# All-in-one_Starter_Kit_for_Micro_bit_V1_.net
KiCad netlist of a schematic drawn in EAGLE
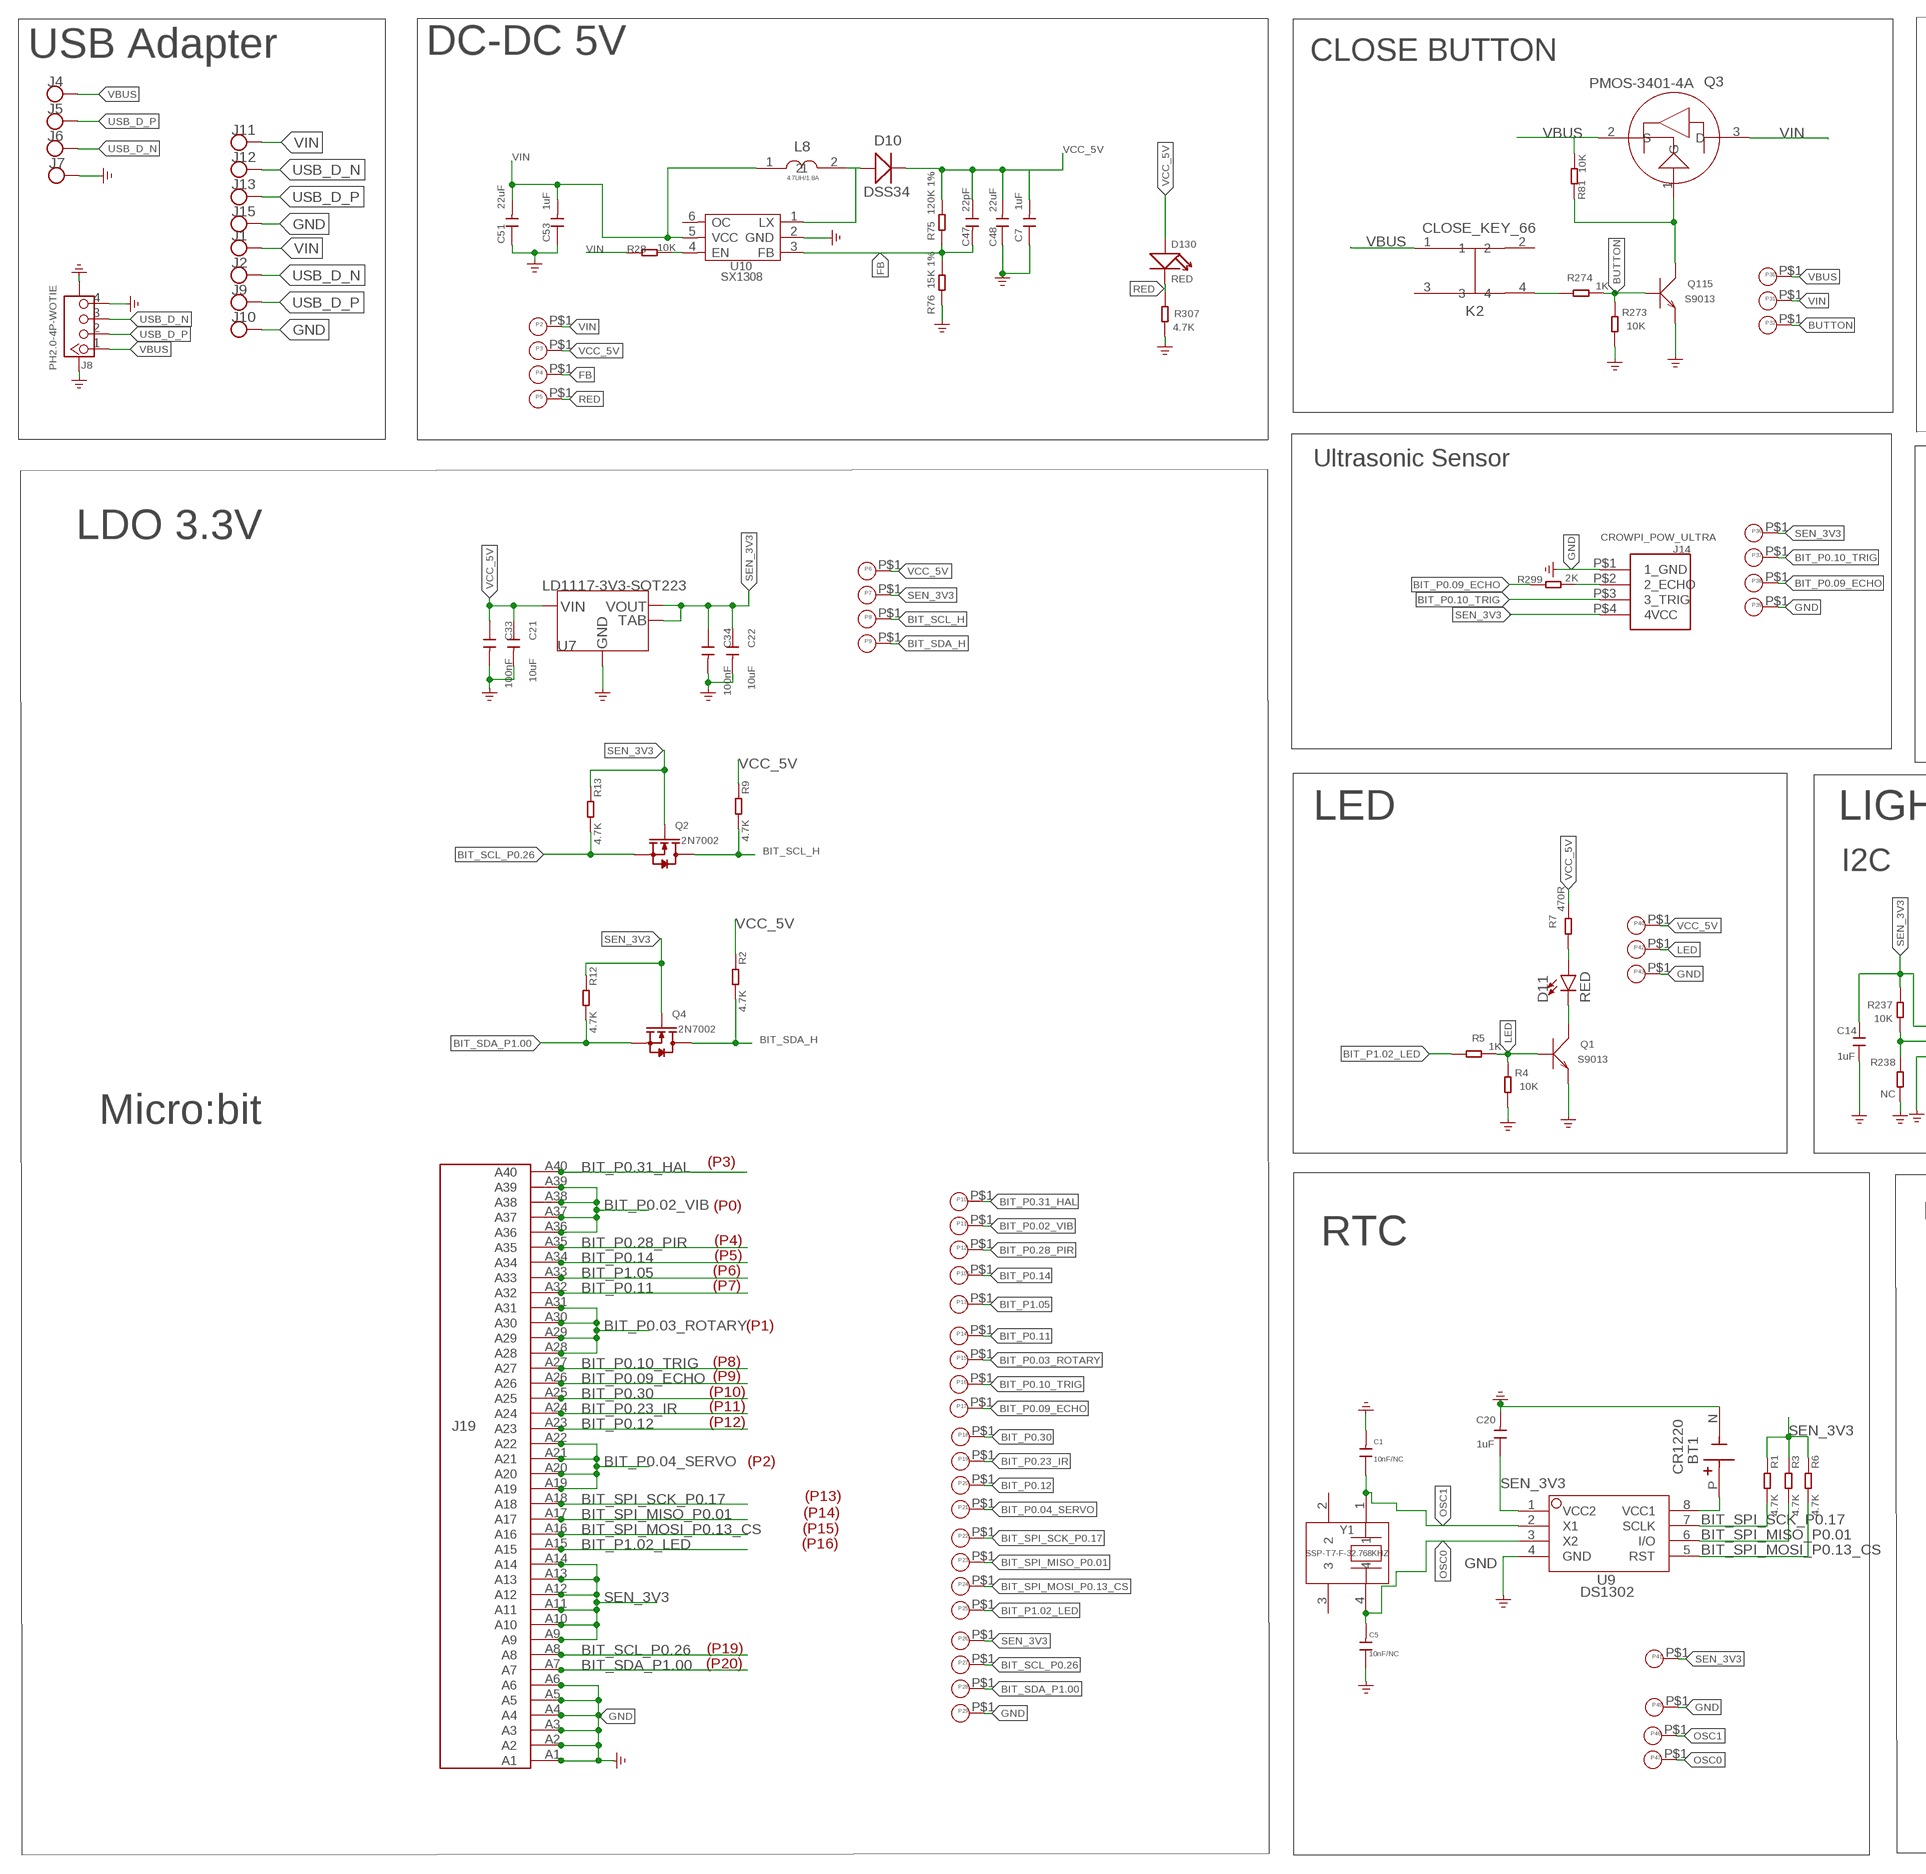
[diagram p0: schematic, sheet 1, part 1 of 2]
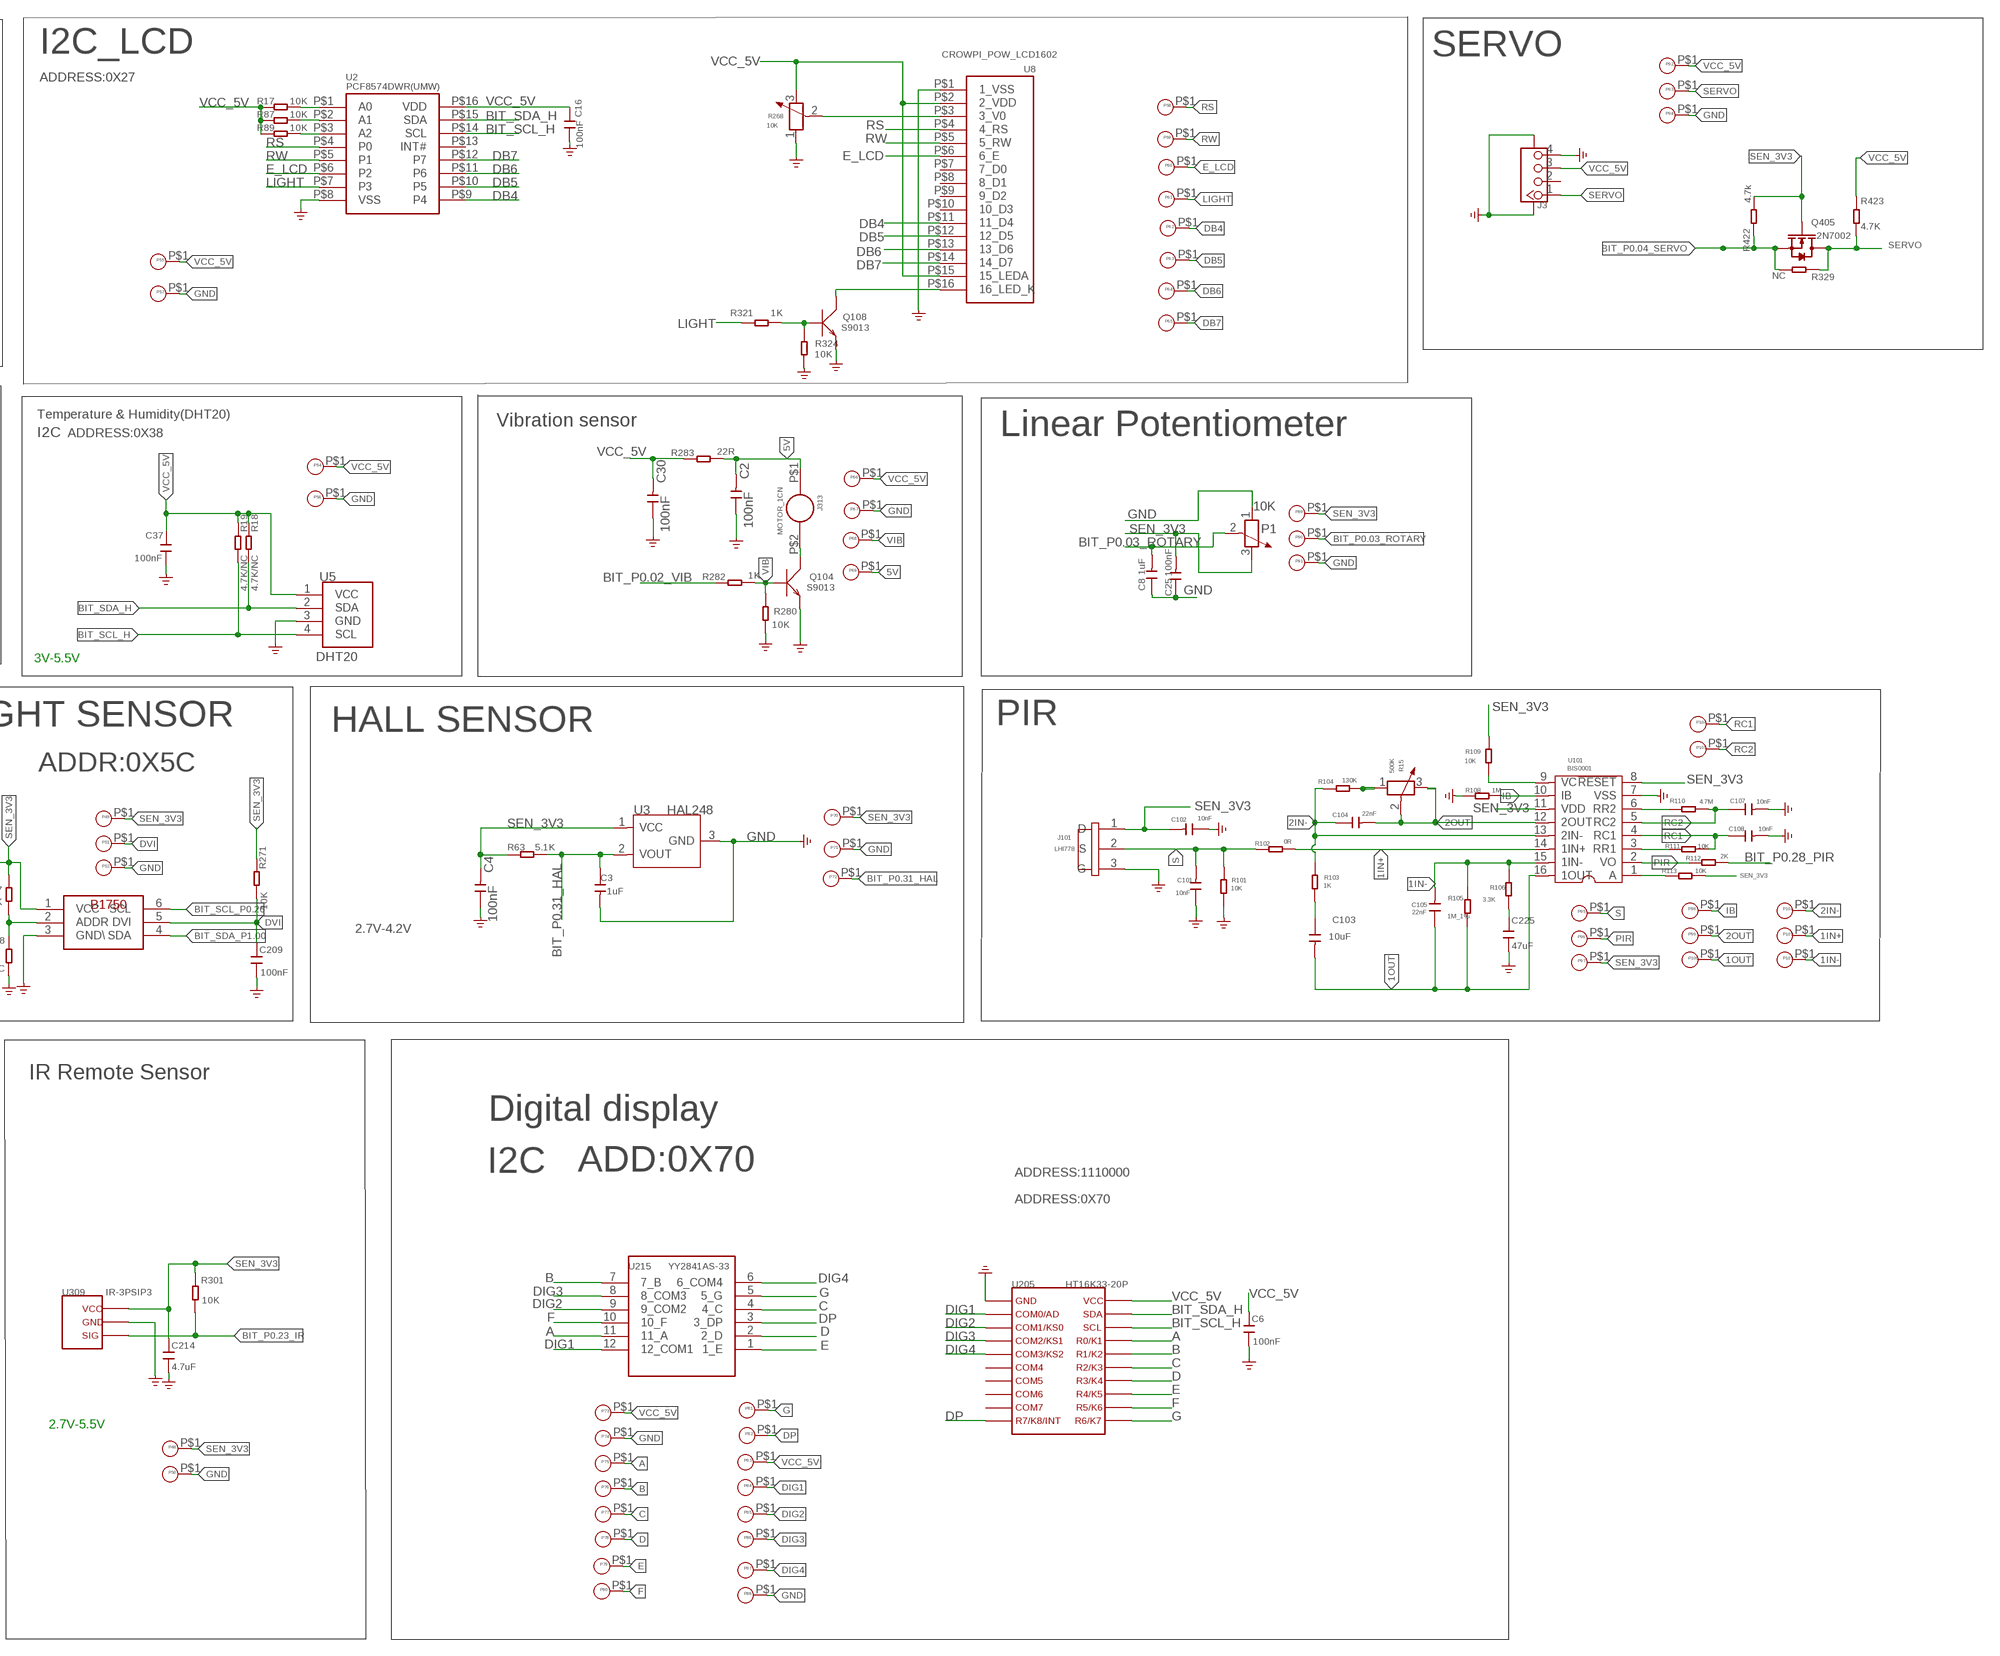
[diagram p1: schematic, sheet 1, part 2 of 2]

(export (version "E")
  (design (tool "Eeschema 10.0.6"))
  (components
    (comp (ref "BT1")
      (value "CR1220")
      (footprint "eagle-import:CR1220")
      (fields (field (name "MF") "Harwin") (field (name "MP") "S8411-45R"))
      (libsource (lib "eagle-import") (part "CR1220"))
    )
    (comp (ref "C1")
      (value "10nF/NC")
      (footprint "eagle-import:C0603")
      (libsource (lib "eagle-import") (part "C-0603"))
    )
    (comp (ref "C2")
      (value "100nF")
      (footprint "eagle-import:C0603")
      (libsource (lib "eagle-import") (part "C-0603"))
    )
    (comp (ref "C3")
      (value "1uF")
      (footprint "eagle-import:C0603")
      (libsource (lib "eagle-import") (part "C-0603"))
    )
    (comp (ref "C4")
      (value "100nF")
      (footprint "eagle-import:C0603")
      (libsource (lib "eagle-import") (part "C-0603"))
    )
    (comp (ref "C5")
      (value "10nF/NC")
      (footprint "eagle-import:C0603")
      (libsource (lib "eagle-import") (part "C-0603"))
    )
    (comp (ref "C6")
      (value "100nF")
      (footprint "eagle-import:0603")
      (libsource (lib "eagle-import") (part "cooper_C0603"))
    )
    (comp (ref "C7")
      (value "1uF")
      (footprint "eagle-import:C0603")
      (libsource (lib "eagle-import") (part "LoraWAN_Gateway_Mainboard_CAP"))
    )
    (comp (ref "C8")
      (value "1uF")
      (footprint "eagle-import:C0603")
      (libsource (lib "eagle-import") (part "C-0603"))
    )
    (comp (ref "C14")
      (value "1uF")
      (footprint "eagle-import:0603")
      (libsource (lib "eagle-import") (part "cooper_C0603"))
    )
    (comp (ref "C16")
      (value "100nF")
      (footprint "eagle-import:0603")
      (libsource (lib "eagle-import") (part "cooper_C0603"))
    )
    (comp (ref "C20")
      (value "1uF")
      (footprint "eagle-import:C0603")
      (libsource (lib "eagle-import") (part "CAP"))
    )
    (comp (ref "C21")
      (value "10uF")
      (footprint "eagle-import:C0603")
      (libsource (lib "eagle-import") (part "LoraWAN_Gateway_Mainboard_CAP"))
    )
    (comp (ref "C22")
      (value "10uF")
      (footprint "eagle-import:C0603")
      (libsource (lib "eagle-import") (part "LoraWAN_Gateway_Mainboard_CAP"))
    )
    (comp (ref "C25")
      (value "100nF")
      (footprint "eagle-import:C0603")
      (libsource (lib "eagle-import") (part "C-0603"))
    )
    (comp (ref "C30")
      (value "100nF")
      (footprint "eagle-import:C0603")
      (libsource (lib "eagle-import") (part "C-0603"))
    )
    (comp (ref "C33")
      (value "100nF")
      (footprint "eagle-import:C0603")
      (libsource (lib "eagle-import") (part "LoraWAN_Gateway_Mainboard_CAP"))
    )
    (comp (ref "C34")
      (value "100nF")
      (footprint "eagle-import:C0603")
      (libsource (lib "eagle-import") (part "LoraWAN_Gateway_Mainboard_CAP"))
    )
    (comp (ref "C37")
      (value "100nF")
      (footprint "eagle-import:0603")
      (libsource (lib "eagle-import") (part "cooper_C0603"))
    )
    (comp (ref "C47")
      (value "22pF")
      (footprint "eagle-import:C0603")
      (libsource (lib "eagle-import") (part "LoraWAN_Gateway_Mainboard_CAP"))
    )
    (comp (ref "C48")
      (value "22uF")
      (footprint "eagle-import:C0805")
      (libsource (lib "eagle-import") (part "LoraWAN_Gateway_Mainboard_CAPC0805"))
    )
    (comp (ref "C51")
      (value "22uF")
      (footprint "eagle-import:C0805")
      (libsource (lib "eagle-import") (part "LoraWAN_Gateway_Mainboard_CAPC0805"))
    )
    (comp (ref "C53")
      (value "1uF")
      (footprint "eagle-import:C0603")
      (libsource (lib "eagle-import") (part "LoraWAN_Gateway_Mainboard_CAP"))
    )
    (comp (ref "C101")
      (value "10nF")
      (footprint "eagle-import:C0603")
      (libsource (lib "eagle-import") (part "C-0603"))
    )
    (comp (ref "C102")
      (value "10nF")
      (footprint "eagle-import:C0603")
      (libsource (lib "eagle-import") (part "C-0603"))
    )
    (comp (ref "C103")
      (value "10uF")
      (footprint "eagle-import:0603")
      (libsource (lib "eagle-import") (part "C0603"))
    )
    (comp (ref "C104")
      (value "22nF")
      (footprint "eagle-import:C0603")
      (libsource (lib "eagle-import") (part "C-0603"))
    )
    (comp (ref "C105")
      (value "22nF")
      (footprint "eagle-import:C0603")
      (libsource (lib "eagle-import") (part "C-0603"))
    )
    (comp (ref "C107")
      (value "10nF")
      (footprint "eagle-import:C0603")
      (libsource (lib "eagle-import") (part "C-0603"))
    )
    (comp (ref "C108")
      (value "10nF")
      (footprint "eagle-import:C0603")
      (libsource (lib "eagle-import") (part "C-0603"))
    )
    (comp (ref "C209")
      (value "100nF")
      (footprint "eagle-import:0603")
      (libsource (lib "eagle-import") (part "cooper_C0603"))
    )
    (comp (ref "C214")
      (value "4.7uF")
      (footprint "eagle-import:0603")
      (libsource (lib "eagle-import") (part "cooper_C0603"))
    )
    (comp (ref "C225")
      (value "47uF")
      (footprint "eagle-import:0805")
      (libsource (lib "eagle-import") (part "C0805"))
    )
    (comp (ref "D10")
      (value "DSS34")
      (footprint "eagle-import:D_SOD123FL")
      (libsource (lib "eagle-import") (part "DIODE"))
    )
    (comp (ref "D11")
      (value "RED")
      (footprint "eagle-import:LED-8MM")
      (libsource (lib "eagle-import") (part "LED"))
    )
    (comp (ref "D130")
      (value "RED")
      (footprint "eagle-import:LED_0603_SMT")
      (libsource (lib "eagle-import") (part "LED_0603_SMT"))
    )
    (comp (ref "J1")
      (value "TP-SMDTP-SMD-2X4MM")
      (footprint "eagle-import:TP-SMD-2X4MM")
      (libsource (lib "eagle-import") (part "TP-SMDTP-SMD-2X4MM"))
    )
    (comp (ref "J2")
      (value "TP-SMDTP-SMD-2X4MM")
      (footprint "eagle-import:TP-SMD-2X4MM")
      (libsource (lib "eagle-import") (part "TP-SMDTP-SMD-2X4MM"))
    )
    (comp (ref "J3")
      (value "A_XBJ_CONNECTOR_TWIG-4P-2.0-SMD-FEMALE-REINFORCE90D")
      (footprint "eagle-import:A_XBJ_CONNECTOR_4P-SMD-2.0-90D")
      (libsource (lib "eagle-import") (part "A_XBJ_CONNECTOR_TWIG-4P-2.0-SMD-FEMALE-REINFORCE90D"))
    )
    (comp (ref "J4")
      (value "TP-SMDTP-SMD-2X4MM")
      (footprint "eagle-import:TP-SMD-2X4MM")
      (libsource (lib "eagle-import") (part "TP-SMDTP-SMD-2X4MM"))
    )
    (comp (ref "J5")
      (value "TP-SMDTP-SMD-2X4MM")
      (footprint "eagle-import:TP-SMD-2X4MM")
      (libsource (lib "eagle-import") (part "TP-SMDTP-SMD-2X4MM"))
    )
    (comp (ref "J6")
      (value "TP-SMDTP-SMD-2X4MM")
      (footprint "eagle-import:TP-SMD-2X4MM")
      (libsource (lib "eagle-import") (part "TP-SMDTP-SMD-2X4MM"))
    )
    (comp (ref "J7")
      (value "TP-SMDTP-SMD-2X4MM")
      (footprint "eagle-import:TP-SMD-2X4MM")
      (libsource (lib "eagle-import") (part "TP-SMDTP-SMD-2X4MM"))
    )
    (comp (ref "J8")
      (value "PH2.0-4P-WOTIE")
      (footprint "eagle-import:PH2.0-4P")
      (libsource (lib "eagle-import") (part "PH2.0-4P-WOTIE"))
    )
    (comp (ref "J9")
      (value "TP-SMDTP-SMD-2X4MM")
      (footprint "eagle-import:TP-SMD-2X4MM")
      (libsource (lib "eagle-import") (part "TP-SMDTP-SMD-2X4MM"))
    )
    (comp (ref "J10")
      (value "TP-SMDTP-SMD-2X4MM")
      (footprint "eagle-import:TP-SMD-2X4MM")
      (libsource (lib "eagle-import") (part "TP-SMDTP-SMD-2X4MM"))
    )
    (comp (ref "J11")
      (value "TP-SMDTP-SMD-2X4MM")
      (footprint "eagle-import:TP-SMD-2X4MM")
      (libsource (lib "eagle-import") (part "TP-SMDTP-SMD-2X4MM"))
    )
    (comp (ref "J12")
      (value "TP-SMDTP-SMD-2X4MM")
      (footprint "eagle-import:TP-SMD-2X4MM")
      (libsource (lib "eagle-import") (part "TP-SMDTP-SMD-2X4MM"))
    )
    (comp (ref "J13")
      (value "TP-SMDTP-SMD-2X4MM")
      (footprint "eagle-import:TP-SMD-2X4MM")
      (libsource (lib "eagle-import") (part "TP-SMDTP-SMD-2X4MM"))
    )
    (comp (ref "J14")
      (value "CROWPI_POW_ULTRA")
      (footprint "eagle-import:CROWPI_POW_ULTRA")
      (libsource (lib "eagle-import") (part "CROWPI_POW_ULTRA"))
    )
    (comp (ref "J15")
      (value "TP-SMDTP-SMD-2X4MM")
      (footprint "eagle-import:TP-SMD-2X4MM")
      (libsource (lib "eagle-import") (part "TP-SMDTP-SMD-2X4MM"))
    )
    (comp (ref "J19")
      (value "MICROBIT_SMD_40P")
      (footprint "eagle-import:MICROBIT_SMD_40P")
      (libsource (lib "eagle-import") (part "MICROBIT_SMD_40P"))
    )
    (comp (ref "J101")
      (value "LHI778")
      (footprint "eagle-import:3P-D8.1MM")
      (libsource (lib "eagle-import") (part "LHI778"))
    )
    (comp (ref "J313")
      (value "MOTOR_1CN")
      (footprint "eagle-import:MOTOR_1CM")
      (libsource (lib "eagle-import") (part "MOTOR_1CN"))
    )
    (comp (ref "K2")
      (value "CLOSE_KEY_66")
      (footprint "eagle-import:CLOSE_KEY_6_6")
      (libsource (lib "eagle-import") (part "CLOSE_KEY_66"))
    )
    (comp (ref "L8")
      (value "4.7UH/1.8A")
      (footprint "eagle-import:1008")
      (libsource (lib "eagle-import") (part "ZEMS252012-4R7M"))
    )
    (comp (ref "P1")
      (value "10K")
      (footprint "eagle-import:3P-SQUA-45.6X10X5.8H")
      (libsource (lib "eagle-import") (part "R-POTENTIOMETER"))
    )
    (comp (ref "P2")
      (value "PADPAD-1.0MM")
      (footprint "eagle-import:PAD-1.0MM")
      (libsource (lib "eagle-import") (part "PADPAD-1.0MM"))
    )
    (comp (ref "P3")
      (value "PADPAD-1.0MM")
      (footprint "eagle-import:PAD-1.0MM")
      (libsource (lib "eagle-import") (part "PADPAD-1.0MM"))
    )
    (comp (ref "P4")
      (value "PADPAD-1.0MM")
      (footprint "eagle-import:PAD-1.0MM")
      (libsource (lib "eagle-import") (part "PADPAD-1.0MM"))
    )
    (comp (ref "P5")
      (value "PADPAD-1.0MM")
      (footprint "eagle-import:PAD-1.0MM")
      (libsource (lib "eagle-import") (part "PADPAD-1.0MM"))
    )
    (comp (ref "P6")
      (value "PADPAD-1.0MM")
      (footprint "eagle-import:PAD-1.0MM")
      (libsource (lib "eagle-import") (part "PADPAD-1.0MM"))
    )
    (comp (ref "P7")
      (value "PADPAD-1.0MM")
      (footprint "eagle-import:PAD-1.0MM")
      (libsource (lib "eagle-import") (part "PADPAD-1.0MM"))
    )
    (comp (ref "P8")
      (value "PADPAD-1.0MM")
      (footprint "eagle-import:PAD-1.0MM")
      (libsource (lib "eagle-import") (part "PADPAD-1.0MM"))
    )
    (comp (ref "P9")
      (value "PADPAD-1.0MM")
      (footprint "eagle-import:PAD-1.0MM")
      (libsource (lib "eagle-import") (part "PADPAD-1.0MM"))
    )
    (comp (ref "P10")
      (value "PADPAD-1.0MM")
      (footprint "eagle-import:PAD-1.0MM")
      (libsource (lib "eagle-import") (part "PADPAD-1.0MM"))
    )
    (comp (ref "P11")
      (value "PADPAD-1.0MM")
      (footprint "eagle-import:PAD-1.0MM")
      (libsource (lib "eagle-import") (part "PADPAD-1.0MM"))
    )
    (comp (ref "P12")
      (value "PADPAD-1.0MM")
      (footprint "eagle-import:PAD-1.0MM")
      (libsource (lib "eagle-import") (part "PADPAD-1.0MM"))
    )
    (comp (ref "P13")
      (value "PADPAD-1.0MM")
      (footprint "eagle-import:PAD-1.0MM")
      (libsource (lib "eagle-import") (part "PADPAD-1.0MM"))
    )
    (comp (ref "P14")
      (value "PADPAD-1.0MM")
      (footprint "eagle-import:PAD-1.0MM")
      (libsource (lib "eagle-import") (part "PADPAD-1.0MM"))
    )
    (comp (ref "P15")
      (value "PADPAD-1.0MM")
      (footprint "eagle-import:PAD-1.0MM")
      (libsource (lib "eagle-import") (part "PADPAD-1.0MM"))
    )
    (comp (ref "P16")
      (value "PADPAD-1.0MM")
      (footprint "eagle-import:PAD-1.0MM")
      (libsource (lib "eagle-import") (part "PADPAD-1.0MM"))
    )
    (comp (ref "P17")
      (value "PADPAD-1.0MM")
      (footprint "eagle-import:PAD-1.0MM")
      (libsource (lib "eagle-import") (part "PADPAD-1.0MM"))
    )
    (comp (ref "P18")
      (value "PADPAD-1.0MM")
      (footprint "eagle-import:PAD-1.0MM")
      (libsource (lib "eagle-import") (part "PADPAD-1.0MM"))
    )
    (comp (ref "P19")
      (value "PADPAD-1.0MM")
      (footprint "eagle-import:PAD-1.0MM")
      (libsource (lib "eagle-import") (part "PADPAD-1.0MM"))
    )
    (comp (ref "P20")
      (value "PADPAD-1.0MM")
      (footprint "eagle-import:PAD-1.0MM")
      (libsource (lib "eagle-import") (part "PADPAD-1.0MM"))
    )
    (comp (ref "P21")
      (value "PADPAD-1.0MM")
      (footprint "eagle-import:PAD-1.0MM")
      (libsource (lib "eagle-import") (part "PADPAD-1.0MM"))
    )
    (comp (ref "P22")
      (value "PADPAD-1.0MM")
      (footprint "eagle-import:PAD-1.0MM")
      (libsource (lib "eagle-import") (part "PADPAD-1.0MM"))
    )
    (comp (ref "P23")
      (value "PADPAD-1.0MM")
      (footprint "eagle-import:PAD-1.0MM")
      (libsource (lib "eagle-import") (part "PADPAD-1.0MM"))
    )
    (comp (ref "P24")
      (value "PADPAD-1.0MM")
      (footprint "eagle-import:PAD-1.0MM")
      (libsource (lib "eagle-import") (part "PADPAD-1.0MM"))
    )
    (comp (ref "P25")
      (value "PADPAD-1.0MM")
      (footprint "eagle-import:PAD-1.0MM")
      (libsource (lib "eagle-import") (part "PADPAD-1.0MM"))
    )
    (comp (ref "P26")
      (value "PADPAD-1.0MM")
      (footprint "eagle-import:PAD-1.0MM")
      (libsource (lib "eagle-import") (part "PADPAD-1.0MM"))
    )
    (comp (ref "P27")
      (value "PADPAD-1.0MM")
      (footprint "eagle-import:PAD-1.0MM")
      (libsource (lib "eagle-import") (part "PADPAD-1.0MM"))
    )
    (comp (ref "P28")
      (value "PADPAD-1.0MM")
      (footprint "eagle-import:PAD-1.0MM")
      (libsource (lib "eagle-import") (part "PADPAD-1.0MM"))
    )
    (comp (ref "P29")
      (value "PADPAD-1.0MM")
      (footprint "eagle-import:PAD-1.0MM")
      (libsource (lib "eagle-import") (part "PADPAD-1.0MM"))
    )
    (comp (ref "P30")
      (value "PADPAD-1.0MM")
      (footprint "eagle-import:PAD-1.0MM")
      (libsource (lib "eagle-import") (part "PADPAD-1.0MM"))
    )
    (comp (ref "P31")
      (value "PADPAD-1.0MM")
      (footprint "eagle-import:PAD-1.0MM")
      (libsource (lib "eagle-import") (part "PADPAD-1.0MM"))
    )
    (comp (ref "P32")
      (value "PADPAD-1.0MM")
      (footprint "eagle-import:PAD-1.0MM")
      (libsource (lib "eagle-import") (part "PADPAD-1.0MM"))
    )
    (comp (ref "P36")
      (value "PADPAD-1.0MM")
      (footprint "eagle-import:PAD-1.0MM")
      (libsource (lib "eagle-import") (part "PADPAD-1.0MM"))
    )
    (comp (ref "P37")
      (value "PADPAD-1.0MM")
      (footprint "eagle-import:PAD-1.0MM")
      (libsource (lib "eagle-import") (part "PADPAD-1.0MM"))
    )
    (comp (ref "P38")
      (value "PADPAD-1.0MM")
      (footprint "eagle-import:PAD-1.0MM")
      (libsource (lib "eagle-import") (part "PADPAD-1.0MM"))
    )
    (comp (ref "P39")
      (value "PADPAD-1.0MM")
      (footprint "eagle-import:PAD-1.0MM")
      (libsource (lib "eagle-import") (part "PADPAD-1.0MM"))
    )
    (comp (ref "P40")
      (value "PADPAD-1.0MM")
      (footprint "eagle-import:PAD-1.0MM")
      (libsource (lib "eagle-import") (part "PADPAD-1.0MM"))
    )
    (comp (ref "P41")
      (value "PADPAD-1.0MM")
      (footprint "eagle-import:PAD-1.0MM")
      (libsource (lib "eagle-import") (part "PADPAD-1.0MM"))
    )
    (comp (ref "P42")
      (value "PADPAD-1.0MM")
      (footprint "eagle-import:PAD-1.0MM")
      (libsource (lib "eagle-import") (part "PADPAD-1.0MM"))
    )
    (comp (ref "P43")
      (value "PADPAD-1.0MM")
      (footprint "eagle-import:PAD-1.0MM")
      (libsource (lib "eagle-import") (part "PADPAD-1.0MM"))
    )
    (comp (ref "P45")
      (value "PADPAD-1.0MM")
      (footprint "eagle-import:PAD-1.0MM")
      (libsource (lib "eagle-import") (part "PADPAD-1.0MM"))
    )
    (comp (ref "P46")
      (value "PADPAD-1.0MM")
      (footprint "eagle-import:PAD-1.0MM")
      (libsource (lib "eagle-import") (part "PADPAD-1.0MM"))
    )
    (comp (ref "P47")
      (value "PADPAD-1.0MM")
      (footprint "eagle-import:PAD-1.0MM")
      (libsource (lib "eagle-import") (part "PADPAD-1.0MM"))
    )
    (comp (ref "P48")
      (value "PADPAD-1.0MM")
      (footprint "eagle-import:PAD-1.0MM")
      (libsource (lib "eagle-import") (part "PADPAD-1.0MM"))
    )
    (comp (ref "P49")
      (value "PADPAD-1.0MM")
      (footprint "eagle-import:PAD-1.0MM")
      (libsource (lib "eagle-import") (part "PADPAD-1.0MM"))
    )
    (comp (ref "P50")
      (value "PADPAD-1.0MM")
      (footprint "eagle-import:PAD-1.0MM")
      (libsource (lib "eagle-import") (part "PADPAD-1.0MM"))
    )
    (comp (ref "P51")
      (value "PADPAD-1.0MM")
      (footprint "eagle-import:PAD-1.0MM")
      (libsource (lib "eagle-import") (part "PADPAD-1.0MM"))
    )
    (comp (ref "P52")
      (value "PADPAD-1.0MM")
      (footprint "eagle-import:PAD-1.0MM")
      (libsource (lib "eagle-import") (part "PADPAD-1.0MM"))
    )
    (comp (ref "P54")
      (value "PADPAD-1.0MM")
      (footprint "eagle-import:PAD-1.0MM")
      (libsource (lib "eagle-import") (part "PADPAD-1.0MM"))
    )
    (comp (ref "P55")
      (value "PADPAD-1.0MM")
      (footprint "eagle-import:PAD-1.0MM")
      (libsource (lib "eagle-import") (part "PADPAD-1.0MM"))
    )
    (comp (ref "P56")
      (value "PADPAD-1.0MM")
      (footprint "eagle-import:PAD-1.0MM")
      (libsource (lib "eagle-import") (part "PADPAD-1.0MM"))
    )
    (comp (ref "P57")
      (value "PADPAD-1.0MM")
      (footprint "eagle-import:PAD-1.0MM")
      (libsource (lib "eagle-import") (part "PADPAD-1.0MM"))
    )
    (comp (ref "P58")
      (value "PADPAD-1.0MM")
      (footprint "eagle-import:PAD-1.0MM")
      (libsource (lib "eagle-import") (part "PADPAD-1.0MM"))
    )
    (comp (ref "P59")
      (value "PADPAD-1.0MM")
      (footprint "eagle-import:PAD-1.0MM")
      (libsource (lib "eagle-import") (part "PADPAD-1.0MM"))
    )
    (comp (ref "P60")
      (value "PADPAD-1.0MM")
      (footprint "eagle-import:PAD-1.0MM")
      (libsource (lib "eagle-import") (part "PADPAD-1.0MM"))
    )
    (comp (ref "P61")
      (value "PADPAD-1.0MM")
      (footprint "eagle-import:PAD-1.0MM")
      (libsource (lib "eagle-import") (part "PADPAD-1.0MM"))
    )
    (comp (ref "P62")
      (value "PADPAD-1.0MM")
      (footprint "eagle-import:PAD-1.0MM")
      (libsource (lib "eagle-import") (part "PADPAD-1.0MM"))
    )
    (comp (ref "P63")
      (value "PADPAD-1.0MM")
      (footprint "eagle-import:PAD-1.0MM")
      (libsource (lib "eagle-import") (part "PADPAD-1.0MM"))
    )
    (comp (ref "P64")
      (value "PADPAD-1.0MM")
      (footprint "eagle-import:PAD-1.0MM")
      (libsource (lib "eagle-import") (part "PADPAD-1.0MM"))
    )
    (comp (ref "P65")
      (value "PADPAD-1.0MM")
      (footprint "eagle-import:PAD-1.0MM")
      (libsource (lib "eagle-import") (part "PADPAD-1.0MM"))
    )
    (comp (ref "P66")
      (value "PADPAD-1.0MM")
      (footprint "eagle-import:PAD-1.0MM")
      (libsource (lib "eagle-import") (part "PADPAD-1.0MM"))
    )
    (comp (ref "P67")
      (value "PADPAD-1.0MM")
      (footprint "eagle-import:PAD-1.0MM")
      (libsource (lib "eagle-import") (part "PADPAD-1.0MM"))
    )
    (comp (ref "P68")
      (value "PADPAD-1.0MM")
      (footprint "eagle-import:PAD-1.0MM")
      (libsource (lib "eagle-import") (part "PADPAD-1.0MM"))
    )
    (comp (ref "P69")
      (value "PADPAD-1.0MM")
      (footprint "eagle-import:PAD-1.0MM")
      (libsource (lib "eagle-import") (part "PADPAD-1.0MM"))
    )
    (comp (ref "P70")
      (value "PADPAD-1.0MM")
      (footprint "eagle-import:PAD-1.0MM")
      (libsource (lib "eagle-import") (part "PADPAD-1.0MM"))
    )
    (comp (ref "P71")
      (value "PADPAD-1.0MM")
      (footprint "eagle-import:PAD-1.0MM")
      (libsource (lib "eagle-import") (part "PADPAD-1.0MM"))
    )
    (comp (ref "P72")
      (value "PADPAD-1.0MM")
      (footprint "eagle-import:PAD-1.0MM")
      (libsource (lib "eagle-import") (part "PADPAD-1.0MM"))
    )
    (comp (ref "P73")
      (value "PADPAD-1.0MM")
      (footprint "eagle-import:PAD-1.0MM")
      (libsource (lib "eagle-import") (part "PADPAD-1.0MM"))
    )
    (comp (ref "P74")
      (value "PADPAD-1.0MM")
      (footprint "eagle-import:PAD-1.0MM")
      (libsource (lib "eagle-import") (part "PADPAD-1.0MM"))
    )
    (comp (ref "P75")
      (value "PADPAD-1.0MM")
      (footprint "eagle-import:PAD-1.0MM")
      (libsource (lib "eagle-import") (part "PADPAD-1.0MM"))
    )
    (comp (ref "P76")
      (value "PADPAD-1.0MM")
      (footprint "eagle-import:PAD-1.0MM")
      (libsource (lib "eagle-import") (part "PADPAD-1.0MM"))
    )
    (comp (ref "P77")
      (value "PADPAD-1.0MM")
      (footprint "eagle-import:PAD-1.0MM")
      (libsource (lib "eagle-import") (part "PADPAD-1.0MM"))
    )
    (comp (ref "P78")
      (value "PADPAD-1.0MM")
      (footprint "eagle-import:PAD-1.0MM")
      (libsource (lib "eagle-import") (part "PADPAD-1.0MM"))
    )
    (comp (ref "P79")
      (value "PADPAD-1.0MM")
      (footprint "eagle-import:PAD-1.0MM")
      (libsource (lib "eagle-import") (part "PADPAD-1.0MM"))
    )
    (comp (ref "P80")
      (value "PADPAD-1.0MM")
      (footprint "eagle-import:PAD-1.0MM")
      (libsource (lib "eagle-import") (part "PADPAD-1.0MM"))
    )
    (comp (ref "P81")
      (value "PADPAD-1.0MM")
      (footprint "eagle-import:PAD-1.0MM")
      (libsource (lib "eagle-import") (part "PADPAD-1.0MM"))
    )
    (comp (ref "P82")
      (value "PADPAD-1.0MM")
      (footprint "eagle-import:PAD-1.0MM")
      (libsource (lib "eagle-import") (part "PADPAD-1.0MM"))
    )
    (comp (ref "P83")
      (value "PADPAD-1.0MM")
      (footprint "eagle-import:PAD-1.0MM")
      (libsource (lib "eagle-import") (part "PADPAD-1.0MM"))
    )
    (comp (ref "P84")
      (value "PADPAD-1.0MM")
      (footprint "eagle-import:PAD-1.0MM")
      (libsource (lib "eagle-import") (part "PADPAD-1.0MM"))
    )
    (comp (ref "P85")
      (value "PADPAD-1.0MM")
      (footprint "eagle-import:PAD-1.0MM")
      (libsource (lib "eagle-import") (part "PADPAD-1.0MM"))
    )
    (comp (ref "P86")
      (value "PADPAD-1.0MM")
      (footprint "eagle-import:PAD-1.0MM")
      (libsource (lib "eagle-import") (part "PADPAD-1.0MM"))
    )
    (comp (ref "P87")
      (value "PADPAD-1.0MM")
      (footprint "eagle-import:PAD-1.0MM")
      (libsource (lib "eagle-import") (part "PADPAD-1.0MM"))
    )
    (comp (ref "P88")
      (value "PADPAD-1.0MM")
      (footprint "eagle-import:PAD-1.0MM")
      (libsource (lib "eagle-import") (part "PADPAD-1.0MM"))
    )
    (comp (ref "P89")
      (value "PADPAD-1.0MM")
      (footprint "eagle-import:PAD-1.0MM")
      (libsource (lib "eagle-import") (part "PADPAD-1.0MM"))
    )
    (comp (ref "P90")
      (value "PADPAD-1.0MM")
      (footprint "eagle-import:PAD-1.0MM")
      (libsource (lib "eagle-import") (part "PADPAD-1.0MM"))
    )
    (comp (ref "P91")
      (value "PADPAD-1.0MM")
      (footprint "eagle-import:PAD-1.0MM")
      (libsource (lib "eagle-import") (part "PADPAD-1.0MM"))
    )
    (comp (ref "P92")
      (value "PADPAD-1.0MM")
      (footprint "eagle-import:PAD-1.0MM")
      (libsource (lib "eagle-import") (part "PADPAD-1.0MM"))
    )
    (comp (ref "P93")
      (value "PADPAD-1.0MM")
      (footprint "eagle-import:PAD-1.0MM")
      (libsource (lib "eagle-import") (part "PADPAD-1.0MM"))
    )
    (comp (ref "P94")
      (value "PADPAD-1.0MM")
      (footprint "eagle-import:PAD-1.0MM")
      (libsource (lib "eagle-import") (part "PADPAD-1.0MM"))
    )
    (comp (ref "P95")
      (value "PADPAD-1.0MM")
      (footprint "eagle-import:PAD-1.0MM")
      (libsource (lib "eagle-import") (part "PADPAD-1.0MM"))
    )
    (comp (ref "P96")
      (value "PADPAD-1.0MM")
      (footprint "eagle-import:PAD-1.0MM")
      (libsource (lib "eagle-import") (part "PADPAD-1.0MM"))
    )
    (comp (ref "P97")
      (value "PADPAD-1.0MM")
      (footprint "eagle-import:PAD-1.0MM")
      (libsource (lib "eagle-import") (part "PADPAD-1.0MM"))
    )
    (comp (ref "P98")
      (value "PADPAD-1.0MM")
      (footprint "eagle-import:PAD-1.0MM")
      (libsource (lib "eagle-import") (part "PADPAD-1.0MM"))
    )
    (comp (ref "P99")
      (value "PADPAD-1.0MM")
      (footprint "eagle-import:PAD-1.0MM")
      (libsource (lib "eagle-import") (part "PADPAD-1.0MM"))
    )
    (comp (ref "P100")
      (value "PADPAD-1.0MM")
      (footprint "eagle-import:PAD-1.0MM")
      (libsource (lib "eagle-import") (part "PADPAD-1.0MM"))
    )
    (comp (ref "P101")
      (value "PADPAD-1.0MM")
      (footprint "eagle-import:PAD-1.0MM")
      (libsource (lib "eagle-import") (part "PADPAD-1.0MM"))
    )
    (comp (ref "P102")
      (value "PADPAD-1.0MM")
      (footprint "eagle-import:PAD-1.0MM")
      (libsource (lib "eagle-import") (part "PADPAD-1.0MM"))
    )
    (comp (ref "P103")
      (value "PADPAD-1.0MM")
      (footprint "eagle-import:PAD-1.0MM")
      (libsource (lib "eagle-import") (part "PADPAD-1.0MM"))
    )
    (comp (ref "P104")
      (value "PADPAD-1.0MM")
      (footprint "eagle-import:PAD-1.0MM")
      (libsource (lib "eagle-import") (part "PADPAD-1.0MM"))
    )
    (comp (ref "P105")
      (value "PADPAD-1.0MM")
      (footprint "eagle-import:PAD-1.0MM")
      (libsource (lib "eagle-import") (part "PADPAD-1.0MM"))
    )
    (comp (ref "P106")
      (value "PADPAD-1.0MM")
      (footprint "eagle-import:PAD-1.0MM")
      (libsource (lib "eagle-import") (part "PADPAD-1.0MM"))
    )
    (comp (ref "Q1")
      (value "S9013")
      (footprint "eagle-import:SOT23@1")
      (libsource (lib "eagle-import") (part "TRANSISTOR-NPN-SOT23"))
    )
    (comp (ref "Q2")
      (value "2N7002")
      (footprint "eagle-import:SOT23")
      (libsource (lib "eagle-import") (part "MOSFET-N'SOT23'"))
    )
    (comp (ref "Q3")
      (value "PMOS-3401-4A")
      (footprint "eagle-import:DFN8_SOT-23")
      (libsource (lib "eagle-import") (part "DFN8_P-MOS-SOT23"))
    )
    (comp (ref "Q4")
      (value "2N7002")
      (footprint "eagle-import:SOT23")
      (libsource (lib "eagle-import") (part "MOSFET-N'SOT23'"))
    )
    (comp (ref "Q104")
      (value "S9013")
      (footprint "eagle-import:SOT23@1")
      (libsource (lib "eagle-import") (part "TRANSISTOR-NPN-SOT23"))
    )
    (comp (ref "Q108")
      (value "S9013")
      (footprint "eagle-import:SOT23@1")
      (libsource (lib "eagle-import") (part "TRANSISTOR-NPN-SOT23"))
    )
    (comp (ref "Q115")
      (value "S9013")
      (footprint "eagle-import:SOT23@1")
      (libsource (lib "eagle-import") (part "TRANSISTOR-NPN-SOT23"))
    )
    (comp (ref "Q405")
      (value "2N7002")
      (footprint "eagle-import:SOT23")
      (libsource (lib "eagle-import") (part "MOSFET-N'SOT23'"))
    )
    (comp (ref "R1")
      (value "4.7K")
      (footprint "eagle-import:R0603")
      (libsource (lib "eagle-import") (part "R0603"))
    )
    (comp (ref "R2")
      (value "4.7K")
      (footprint "eagle-import:R0603")
      (libsource (lib "eagle-import") (part "R0603"))
    )
    (comp (ref "R3")
      (value "4.7K")
      (footprint "eagle-import:R0603")
      (libsource (lib "eagle-import") (part "R0603"))
    )
    (comp (ref "R4")
      (value "10K")
      (footprint "eagle-import:R0603")
      (libsource (lib "eagle-import") (part "R-0603"))
    )
    (comp (ref "R5")
      (value "1K")
      (footprint "eagle-import:R0603")
      (libsource (lib "eagle-import") (part "R-0603"))
    )
    (comp (ref "R6")
      (value "4.7K")
      (footprint "eagle-import:R0603")
      (libsource (lib "eagle-import") (part "R0603"))
    )
    (comp (ref "R7")
      (value "470R")
      (footprint "eagle-import:R0603")
      (libsource (lib "eagle-import") (part "R-0603"))
    )
    (comp (ref "R9")
      (value "4.7K")
      (footprint "eagle-import:R0603")
      (libsource (lib "eagle-import") (part "R0603"))
    )
    (comp (ref "R12")
      (value "4.7K")
      (footprint "eagle-import:R0603")
      (libsource (lib "eagle-import") (part "R0603"))
    )
    (comp (ref "R13")
      (value "4.7K")
      (footprint "eagle-import:R0603")
      (libsource (lib "eagle-import") (part "R0603"))
    )
    (comp (ref "R15")
      (value "500K")
      (footprint "eagle-import:3P-SMD-SQUA-3.6X3.3")
      (libsource (lib "eagle-import") (part "R-POTENTIOMETER-SMD"))
    )
    (comp (ref "R17")
      (value "10K")
      (footprint "eagle-import:R0603")
      (libsource (lib "eagle-import") (part "R0603"))
    )
    (comp (ref "R18")
      (value "4.7K/NC")
      (footprint "eagle-import:R0603")
      (libsource (lib "eagle-import") (part "R0603"))
    )
    (comp (ref "R19")
      (value "4.7K/NC")
      (footprint "eagle-import:R0603")
      (libsource (lib "eagle-import") (part "R0603"))
    )
    (comp (ref "R28")
      (value "10K")
      (footprint "eagle-import:R0603-SP")
      (libsource (lib "eagle-import") (part "RES-0603"))
    )
    (comp (ref "R63")
      (value "5.1K")
      (footprint "eagle-import:R0603")
      (libsource (lib "eagle-import") (part "R-0603"))
    )
    (comp (ref "R75")
      (value "120K 1%")
      (footprint "eagle-import:R0603-SP")
      (libsource (lib "eagle-import") (part "RES-0603"))
    )
    (comp (ref "R76")
      (value "15K 1%")
      (footprint "eagle-import:R0603-SP")
      (libsource (lib "eagle-import") (part "RES-0603"))
    )
    (comp (ref "R81")
      (value "10K")
      (footprint "eagle-import:DISCRETE_R0603")
      (libsource (lib "eagle-import") (part "DISCRETE_R-0603"))
    )
    (comp (ref "R87")
      (value "10K")
      (footprint "eagle-import:R0603")
      (libsource (lib "eagle-import") (part "R0603"))
    )
    (comp (ref "R89")
      (value "10K")
      (footprint "eagle-import:R0603")
      (libsource (lib "eagle-import") (part "R0603"))
    )
    (comp (ref "R101")
      (value "10K")
      (footprint "eagle-import:R0603")
      (libsource (lib "eagle-import") (part "R-0603"))
    )
    (comp (ref "R102")
      (value "0R")
      (footprint "eagle-import:R0603")
      (libsource (lib "eagle-import") (part "R-0603"))
    )
    (comp (ref "R103")
      (value "1K")
      (footprint "eagle-import:R0603")
      (libsource (lib "eagle-import") (part "R-0603"))
    )
    (comp (ref "R104")
      (value "130K")
      (footprint "eagle-import:R0603")
      (libsource (lib "eagle-import") (part "R-0603"))
    )
    (comp (ref "R105")
      (value "1M_1%")
      (footprint "eagle-import:R0603")
      (libsource (lib "eagle-import") (part "R-0603"))
    )
    (comp (ref "R106")
      (value "3.3K")
      (footprint "eagle-import:R0603")
      (libsource (lib "eagle-import") (part "R-0603"))
    )
    (comp (ref "R108")
      (value "1M")
      (footprint "eagle-import:R0603")
      (libsource (lib "eagle-import") (part "R-0603"))
    )
    (comp (ref "R109")
      (value "10K")
      (footprint "eagle-import:R0603")
      (libsource (lib "eagle-import") (part "R-0603"))
    )
    (comp (ref "R110")
      (value "4.7M")
      (footprint "eagle-import:R0603")
      (libsource (lib "eagle-import") (part "R-0603"))
    )
    (comp (ref "R111")
      (value "10K")
      (footprint "eagle-import:R0603")
      (libsource (lib "eagle-import") (part "R-0603"))
    )
    (comp (ref "R112")
      (value "2K")
      (footprint "eagle-import:R0603")
      (libsource (lib "eagle-import") (part "R-0603"))
    )
    (comp (ref "R113")
      (value "10K")
      (footprint "eagle-import:R0603")
      (libsource (lib "eagle-import") (part "R-0603"))
    )
    (comp (ref "R237")
      (value "10K")
      (footprint "eagle-import:R0603")
      (libsource (lib "eagle-import") (part "R0603"))
    )
    (comp (ref "R238")
      (value "NC")
      (footprint "eagle-import:R0603")
      (libsource (lib "eagle-import") (part "R0603"))
    )
    (comp (ref "R268")
      (value "10K")
      (footprint "eagle-import:3P-SMD-SQUA-3.6X3.3")
      (libsource (lib "eagle-import") (part "R-POTENTIOMETER-SMD"))
    )
    (comp (ref "R271")
      (value "10K")
      (footprint "eagle-import:R0603")
      (libsource (lib "eagle-import") (part "R0603"))
    )
    (comp (ref "R273")
      (value "10K")
      (footprint "eagle-import:R0603")
      (libsource (lib "eagle-import") (part "R-0603"))
    )
    (comp (ref "R274")
      (value "1K")
      (footprint "eagle-import:R0603")
      (libsource (lib "eagle-import") (part "R-0603"))
    )
    (comp (ref "R280")
      (value "10K")
      (footprint "eagle-import:R0603")
      (libsource (lib "eagle-import") (part "R0603"))
    )
    (comp (ref "R282")
      (value "1K")
      (footprint "eagle-import:R0603")
      (libsource (lib "eagle-import") (part "R0603"))
    )
    (comp (ref "R283")
      (value "22R")
      (footprint "eagle-import:R0603")
      (libsource (lib "eagle-import") (part "R0603"))
    )
    (comp (ref "R299")
      (value "2K")
      (footprint "eagle-import:R0603")
      (libsource (lib "eagle-import") (part "R0603"))
    )
    (comp (ref "R301")
      (value "10K")
      (footprint "eagle-import:R0603")
      (libsource (lib "eagle-import") (part "R0603"))
    )
    (comp (ref "R307")
      (value "4.7K")
      (footprint "eagle-import:R0603")
      (libsource (lib "eagle-import") (part "R0603"))
    )
    (comp (ref "R321")
      (value "1K")
      (footprint "eagle-import:R0603")
      (libsource (lib "eagle-import") (part "R0603"))
    )
    (comp (ref "R324")
      (value "10K")
      (footprint "eagle-import:R0603")
      (libsource (lib "eagle-import") (part "R0603"))
    )
    (comp (ref "R329")
      (value "NC")
      (footprint "eagle-import:R0603")
      (libsource (lib "eagle-import") (part "RESR0603"))
    )
    (comp (ref "R422")
      (value "4.7k")
      (footprint "eagle-import:R0603")
      (libsource (lib "eagle-import") (part "RESR0603"))
    )
    (comp (ref "R423")
      (value "4.7K")
      (footprint "eagle-import:R0603")
      (libsource (lib "eagle-import") (part "RESR0603"))
    )
    (comp (ref "U1")
      (value "BH1750")
      (footprint "eagle-import:BH1750-WSOF-6")
      (libsource (lib "eagle-import") (part "BH1750"))
    )
    (comp (ref "U2")
      (value "PCF8574DWR(UMW)")
      (footprint "eagle-import:SO-16-300MIL")
      (libsource (lib "eagle-import") (part "PCF8574T/TR"))
    )
    (comp (ref "U3")
      (value "HAL248")
      (footprint "eagle-import:SOT-23W")
      (libsource (lib "eagle-import") (part "A1101"))
    )
    (comp (ref "U5")
      (value "DHT20")
      (footprint "eagle-import:CROWTAIL-DHT20-V1.0-20211013_DHT20")
      (libsource (lib "eagle-import") (part "CROWTAIL-DHT20-V1.0-20211013_DHT20"))
    )
    (comp (ref "U7")
      (value "LD1117-3V3-SOT223")
      (footprint "eagle-import:SOT223")
      (libsource (lib "eagle-import") (part "LD1117-3V3-SOT223"))
    )
    (comp (ref "U8")
      (value "CROWPI_POW_LCD1602")
      (footprint "eagle-import:CROWPI_POW_LCD1206")
      (libsource (lib "eagle-import") (part "CROWPI_POW_LCD1602"))
    )
    (comp (ref "U9")
      (value "DS1302")
      (footprint "eagle-import:SOP8")
      (libsource (lib "eagle-import") (part "DS1302"))
    )
    (comp (ref "U10")
      (value "SX1308")
      (footprint "eagle-import:SOT23-6L")
      (libsource (lib "eagle-import") (part "STUDY_SX1301"))
    )
    (comp (ref "U101")
      (value "BIS0001")
      (footprint "eagle-import:SOP16")
      (libsource (lib "eagle-import") (part "TM2291"))
    )
    (comp (ref "U205")
      (value "HT16K33-20P")
      (footprint "eagle-import:HT16K33-SOP20")
      (libsource (lib "eagle-import") (part "HT16K33-20P"))
    )
    (comp (ref "U215")
      (value "YY2841AS-33")
      (footprint "eagle-import:4-DIGITAL_DISPLAY")
      (libsource (lib "eagle-import") (part "4-DIGITAL_DISPLAY"))
    )
    (comp (ref "U309")
      (value "IR-3PSIP3")
      (footprint "eagle-import:VS1838B-SIP3")
      (libsource (lib "eagle-import") (part "IR-3PSIP3"))
    )
    (comp (ref "Y1")
      (value "SSP-T7-F-32.768KHZ")
      (footprint "eagle-import:MC-146")
      (libsource (lib "eagle-import") (part "SSP-T7-F-32.768KHZ"))
    )
  )
  (nets
    (net (code "1") (name "1IN+") (class "Default")
      (node (ref "P102") (pin "P$1") (pinfunction "P$1_P$1") (pintype "bidirectional"))
      (node (ref "R102") (pin "1") (pinfunction "1_1") (pintype "passive"))
      (node (ref "U101") (pin "14") (pinfunction "1IN+_14") (pintype "input"))
    )
    (net (code "2") (name "1IN-") (class "Default")
      (node (ref "C105") (pin "2") (pinfunction "2_2") (pintype "passive"))
      (node (ref "P103") (pin "P$1") (pinfunction "P$1_P$1") (pintype "bidirectional"))
      (node (ref "R105") (pin "2") (pinfunction "2_2") (pintype "passive"))
      (node (ref "R106") (pin "2") (pinfunction "2_2") (pintype "passive"))
      (node (ref "U101") (pin "15") (pinfunction "1IN-_15") (pintype "input"))
    )
    (net (code "3") (name "1OUT") (class "Default")
      (node (ref "C103") (pin "2") (pinfunction "2_2") (pintype "passive"))
      (node (ref "C105") (pin "1") (pinfunction "1_1") (pintype "passive"))
      (node (ref "P100") (pin "P$1") (pinfunction "P$1_P$1") (pintype "bidirectional"))
      (node (ref "R105") (pin "1") (pinfunction "1_1") (pintype "passive"))
      (node (ref "U101") (pin "16") (pinfunction "1OUT_16") (pintype "output"))
    )
    (net (code "4") (name "2IN-") (class "Default")
      (node (ref "C104") (pin "1") (pinfunction "1_1") (pintype "passive"))
      (node (ref "P101") (pin "P$1") (pinfunction "P$1_P$1") (pintype "bidirectional"))
      (node (ref "R103") (pin "2") (pinfunction "2_2") (pintype "passive"))
      (node (ref "R104") (pin "2") (pinfunction "2_2") (pintype "passive"))
      (node (ref "U101") (pin "13") (pinfunction "2IN-_13") (pintype "input"))
    )
    (net (code "5") (name "2OUT") (class "Default")
      (node (ref "C104") (pin "2") (pinfunction "2_2") (pintype "passive"))
      (node (ref "P99") (pin "P$1") (pinfunction "P$1_P$1") (pintype "bidirectional"))
      (node (ref "R15") (pin "2") (pinfunction "3_2") (pintype "passive"))
      (node (ref "R15") (pin "3") (pinfunction "2_3") (pintype "passive"))
      (node (ref "U101") (pin "12") (pinfunction "2OUT_12") (pintype "output"))
    )
    (net (code "6") (name "5V") (class "Default")
      (node (ref "C2") (pin "2") (pinfunction "2_2") (pintype "passive"))
      (node (ref "J313") (pin "P$1") (pinfunction "P$1_P$1") (pintype "bidirectional"))
      (node (ref "P69") (pin "P$1") (pinfunction "P$1_P$1") (pintype "bidirectional"))
      (node (ref "R283") (pin "2") (pinfunction "2_2") (pintype "passive"))
    )
    (net (code "7") (name "A") (class "Default")
      (node (ref "P75") (pin "P$1") (pinfunction "P$1_P$1") (pintype "bidirectional"))
      (node (ref "U205") (pin "P$17") (pinfunction "P$17_P$17") (pintype "bidirectional"))
      (node (ref "U215") (pin "11") (pinfunction "11_A_11") (pintype "bidirectional"))
    )
    (net (code "8") (name "B") (class "Default")
      (node (ref "P76") (pin "P$1") (pinfunction "P$1_P$1") (pintype "bidirectional"))
      (node (ref "U205") (pin "P$16") (pinfunction "P$16_P$16") (pintype "bidirectional"))
      (node (ref "U215") (pin "7") (pinfunction "7_B_7") (pintype "bidirectional"))
    )
    (net (code "9") (name "BIT_P0.02_VIB") (class "Default")
      (node (ref "J19") (pin "A36") (pinfunction "A36_A36") (pintype "bidirectional"))
      (node (ref "J19") (pin "A37") (pinfunction "A37_A37") (pintype "bidirectional"))
      (node (ref "J19") (pin "A38") (pinfunction "A38_A38") (pintype "bidirectional"))
      (node (ref "J19") (pin "A39") (pinfunction "A39_A39") (pintype "bidirectional"))
      (node (ref "P11") (pin "P$1") (pinfunction "P$1_P$1") (pintype "bidirectional"))
      (node (ref "R282") (pin "1") (pinfunction "1_1") (pintype "passive"))
    )
    (net (code "10") (name "BIT_P0.03_ROTARY") (class "Default")
      (node (ref "C8") (pin "2") (pinfunction "2_2") (pintype "passive"))
      (node (ref "J19") (pin "A28") (pinfunction "A28_A28") (pintype "bidirectional"))
      (node (ref "J19") (pin "A29") (pinfunction "A29_A29") (pintype "bidirectional"))
      (node (ref "J19") (pin "A30") (pinfunction "A30_A30") (pintype "bidirectional"))
      (node (ref "J19") (pin "A31") (pinfunction "A31_A31") (pintype "bidirectional"))
      (node (ref "P1") (pin "2") (pinfunction "3_2") (pintype "passive"))
      (node (ref "P15") (pin "P$1") (pinfunction "P$1_P$1") (pintype "bidirectional"))
      (node (ref "P90") (pin "P$1") (pinfunction "P$1_P$1") (pintype "bidirectional"))
    )
    (net (code "11") (name "BIT_P0.04_SERVO") (class "Default")
      (node (ref "J19") (pin "A19") (pinfunction "A19_A19") (pintype "bidirectional"))
      (node (ref "J19") (pin "A20") (pinfunction "A20_A20") (pintype "bidirectional"))
      (node (ref "J19") (pin "A21") (pinfunction "A21_A21") (pintype "bidirectional"))
      (node (ref "J19") (pin "A22") (pinfunction "A22_A22") (pintype "bidirectional"))
      (node (ref "P21") (pin "P$1") (pinfunction "P$1_P$1") (pintype "bidirectional"))
      (node (ref "Q405") (pin "2") (pinfunction "S_2") (pintype "passive"))
      (node (ref "R329") (pin "2") (pinfunction "2_2") (pintype "passive"))
      (node (ref "R422") (pin "1") (pinfunction "1_1") (pintype "passive"))
    )
    (net (code "12") (name "BIT_P0.09_ECHO") (class "Default")
      (node (ref "J19") (pin "A26") (pinfunction "A26_A26") (pintype "bidirectional"))
      (node (ref "P17") (pin "P$1") (pinfunction "P$1_P$1") (pintype "bidirectional"))
      (node (ref "P38") (pin "P$1") (pinfunction "P$1_P$1") (pintype "bidirectional"))
      (node (ref "R299") (pin "2") (pinfunction "2_2") (pintype "passive"))
    )
    (net (code "13") (name "BIT_P0.10_TRIG") (class "Default")
      (node (ref "J14") (pin "P$3") (pinfunction "3_TRIG_P$3") (pintype "bidirectional"))
      (node (ref "J19") (pin "A27") (pinfunction "A27_A27") (pintype "bidirectional"))
      (node (ref "P16") (pin "P$1") (pinfunction "P$1_P$1") (pintype "bidirectional"))
      (node (ref "P37") (pin "P$1") (pinfunction "P$1_P$1") (pintype "bidirectional"))
    )
    (net (code "14") (name "BIT_P0.11") (class "Default")
      (node (ref "J19") (pin "A32") (pinfunction "A32_A32") (pintype "bidirectional"))
      (node (ref "P14") (pin "P$1") (pinfunction "P$1_P$1") (pintype "bidirectional"))
    )
    (net (code "15") (name "BIT_P0.12") (class "Default")
      (node (ref "J19") (pin "A23") (pinfunction "A23_A23") (pintype "bidirectional"))
      (node (ref "P20") (pin "P$1") (pinfunction "P$1_P$1") (pintype "bidirectional"))
    )
    (net (code "16") (name "BIT_P0.14") (class "Default")
      (node (ref "J19") (pin "A34") (pinfunction "A34_A34") (pintype "bidirectional"))
      (node (ref "P106") (pin "P$1") (pinfunction "P$1_P$1") (pintype "bidirectional"))
    )
    (net (code "17") (name "BIT_P0.23_IR") (class "Default")
      (node (ref "J19") (pin "A24") (pinfunction "A24_A24") (pintype "bidirectional"))
      (node (ref "P19") (pin "P$1") (pinfunction "P$1_P$1") (pintype "bidirectional"))
      (node (ref "R301") (pin "2") (pinfunction "2_2") (pintype "passive"))
      (node (ref "U309") (pin "3") (pinfunction "P$3_3") (pintype "bidirectional"))
    )
    (net (code "18") (name "BIT_P0.28_PIR") (class "Default")
      (node (ref "J19") (pin "A35") (pinfunction "A35_A35") (pintype "bidirectional"))
      (node (ref "P12") (pin "P$1") (pinfunction "P$1_P$1") (pintype "bidirectional"))
      (node (ref "R112") (pin "1") (pinfunction "1_1") (pintype "passive"))
    )
    (net (code "19") (name "BIT_P0.30") (class "Default")
      (node (ref "J19") (pin "A25") (pinfunction "A25_A25") (pintype "bidirectional"))
      (node (ref "P18") (pin "P$1") (pinfunction "P$1_P$1") (pintype "bidirectional"))
    )
    (net (code "20") (name "BIT_P0.31_HAL") (class "Default")
      (node (ref "C3") (pin "1") (pinfunction "1_1") (pintype "passive"))
      (node (ref "J19") (pin "A40") (pinfunction "A40_A40") (pintype "bidirectional"))
      (node (ref "P10") (pin "P$1") (pinfunction "P$1_P$1") (pintype "bidirectional"))
      (node (ref "P72") (pin "P$1") (pinfunction "P$1_P$1") (pintype "bidirectional"))
      (node (ref "R63") (pin "1") (pinfunction "1_1") (pintype "passive"))
      (node (ref "U3") (pin "2") (pinfunction "VOUT_2") (pintype "output"))
    )
    (net (code "21") (name "BIT_P1.02_LED") (class "Default")
      (node (ref "J19") (pin "A15") (pinfunction "A15_A15") (pintype "bidirectional"))
      (node (ref "P25") (pin "P$1") (pinfunction "P$1_P$1") (pintype "bidirectional"))
      (node (ref "R5") (pin "2") (pinfunction "2_2") (pintype "passive"))
    )
    (net (code "22") (name "BIT_P1.05") (class "Default")
      (node (ref "J19") (pin "A33") (pinfunction "A33_A33") (pintype "bidirectional"))
      (node (ref "P13") (pin "P$1") (pinfunction "P$1_P$1") (pintype "bidirectional"))
    )
    (net (code "23") (name "BIT_SCL_H") (class "Default")
      (node (ref "P8") (pin "P$1") (pinfunction "P$1_P$1") (pintype "bidirectional"))
      (node (ref "Q2") (pin "3") (pinfunction "D_3") (pintype "passive"))
      (node (ref "R19") (pin "2") (pinfunction "2_2") (pintype "passive"))
      (node (ref "R9") (pin "2") (pinfunction "2_2") (pintype "passive"))
      (node (ref "U2") (pin "P$14") (pinfunction "SCL_P$14") (pintype "bidirectional"))
      (node (ref "U205") (pin "P$18") (pinfunction "P$18_P$18") (pintype "bidirectional"))
      (node (ref "U5") (pin "4") (pinfunction "SCL_4") (pintype "bidirectional"))
    )
    (net (code "24") (name "BIT_SCL_P0.26") (class "Default")
      (node (ref "J19") (pin "A8") (pinfunction "A8_A8") (pintype "bidirectional"))
      (node (ref "P27") (pin "P$1") (pinfunction "P$1_P$1") (pintype "bidirectional"))
      (node (ref "Q2") (pin "2") (pinfunction "S_2") (pintype "passive"))
      (node (ref "R13") (pin "2") (pinfunction "2_2") (pintype "passive"))
      (node (ref "U1") (pin "6") (pinfunction "SCL_6") (pintype "bidirectional"))
    )
    (net (code "25") (name "BIT_SDA_H") (class "Default")
      (node (ref "P9") (pin "P$1") (pinfunction "P$1_P$1") (pintype "bidirectional"))
      (node (ref "Q4") (pin "3") (pinfunction "D_3") (pintype "passive"))
      (node (ref "R18") (pin "2") (pinfunction "2_2") (pintype "passive"))
      (node (ref "R2") (pin "2") (pinfunction "2_2") (pintype "passive"))
      (node (ref "U2") (pin "P$15") (pinfunction "SDA_P$15") (pintype "bidirectional"))
      (node (ref "U205") (pin "P$19") (pinfunction "P$19_P$19") (pintype "bidirectional"))
      (node (ref "U5") (pin "2") (pinfunction "SDA_2") (pintype "bidirectional"))
    )
    (net (code "26") (name "BIT_SDA_P1.00") (class "Default")
      (node (ref "J19") (pin "A7") (pinfunction "A7_A7") (pintype "bidirectional"))
      (node (ref "P28") (pin "P$1") (pinfunction "P$1_P$1") (pintype "bidirectional"))
      (node (ref "Q4") (pin "2") (pinfunction "S_2") (pintype "passive"))
      (node (ref "R12") (pin "2") (pinfunction "2_2") (pintype "passive"))
      (node (ref "U1") (pin "4") (pinfunction "SDA_4") (pintype "bidirectional"))
    )
    (net (code "27") (name "BIT_SPI_MISO_P0.01") (class "Default")
      (node (ref "J19") (pin "A17") (pinfunction "A17_A17") (pintype "bidirectional"))
      (node (ref "P23") (pin "P$1") (pinfunction "P$1_P$1") (pintype "bidirectional"))
      (node (ref "R3") (pin "2") (pinfunction "2_2") (pintype "passive"))
      (node (ref "U9") (pin "6") (pinfunction "I/O_6") (pintype "bidirectional"))
    )
    (net (code "28") (name "BIT_SPI_MOSI_P0.13_CS") (class "Default")
      (node (ref "J19") (pin "A16") (pinfunction "A16_A16") (pintype "bidirectional"))
      (node (ref "P24") (pin "P$1") (pinfunction "P$1_P$1") (pintype "bidirectional"))
      (node (ref "R6") (pin "2") (pinfunction "2_2") (pintype "passive"))
      (node (ref "U9") (pin "5") (pinfunction "RST_5") (pintype "bidirectional"))
    )
    (net (code "29") (name "BIT_SPI_SCK_P0.17") (class "Default")
      (node (ref "J19") (pin "A18") (pinfunction "A18_A18") (pintype "bidirectional"))
      (node (ref "P22") (pin "P$1") (pinfunction "P$1_P$1") (pintype "bidirectional"))
      (node (ref "R1") (pin "2") (pinfunction "2_2") (pintype "passive"))
      (node (ref "U9") (pin "7") (pinfunction "SCLK_7") (pintype "bidirectional"))
    )
    (net (code "30") (name "BUTTON") (class "Default")
      (node (ref "P32") (pin "P$1") (pinfunction "P$1_P$1") (pintype "bidirectional"))
      (node (ref "Q115") (pin "1") (pinfunction "B_1") (pintype "passive"))
      (node (ref "R273") (pin "2") (pinfunction "2_2") (pintype "passive"))
      (node (ref "R274") (pin "1") (pinfunction "1_1") (pintype "passive"))
    )
    (net (code "31") (name "C") (class "Default")
      (node (ref "P77") (pin "P$1") (pinfunction "P$1_P$1") (pintype "bidirectional"))
      (node (ref "U205") (pin "P$15") (pinfunction "P$15_P$15") (pintype "bidirectional"))
      (node (ref "U215") (pin "4") (pinfunction "4_C_4") (pintype "bidirectional"))
    )
    (net (code "32") (name "D") (class "Default")
      (node (ref "P78") (pin "P$1") (pinfunction "P$1_P$1") (pintype "bidirectional"))
      (node (ref "U205") (pin "P$14") (pinfunction "P$14_P$14") (pintype "bidirectional"))
      (node (ref "U215") (pin "2") (pinfunction "2_D_2") (pintype "bidirectional"))
    )
    (net (code "33") (name "DB4") (class "Default")
      (node (ref "P62") (pin "P$1") (pinfunction "P$1_P$1") (pintype "bidirectional"))
      (node (ref "U2") (pin "P$9") (pinfunction "P4_P$9") (pintype "bidirectional"))
      (node (ref "U8") (pin "P$11") (pinfunction "11_D4_P$11") (pintype "bidirectional"))
    )
    (net (code "34") (name "DB5") (class "Default")
      (node (ref "P63") (pin "P$1") (pinfunction "P$1_P$1") (pintype "bidirectional"))
      (node (ref "U2") (pin "P$10") (pinfunction "P5_P$10") (pintype "bidirectional"))
      (node (ref "U8") (pin "P$12") (pinfunction "12_D5_P$12") (pintype "bidirectional"))
    )
    (net (code "35") (name "DB6") (class "Default")
      (node (ref "P64") (pin "P$1") (pinfunction "P$1_P$1") (pintype "bidirectional"))
      (node (ref "U2") (pin "P$11") (pinfunction "P6_P$11") (pintype "bidirectional"))
      (node (ref "U8") (pin "P$13") (pinfunction "13_D6_P$13") (pintype "bidirectional"))
    )
    (net (code "36") (name "DB7") (class "Default")
      (node (ref "P65") (pin "P$1") (pinfunction "P$1_P$1") (pintype "bidirectional"))
      (node (ref "U2") (pin "P$12") (pinfunction "P7_P$12") (pintype "bidirectional"))
      (node (ref "U8") (pin "P$14") (pinfunction "14_D7_P$14") (pintype "bidirectional"))
    )
    (net (code "37") (name "DIG1") (class "Default")
      (node (ref "P84") (pin "P$1") (pinfunction "P$1_P$1") (pintype "bidirectional"))
      (node (ref "U205") (pin "P$2") (pinfunction "P$2_P$2") (pintype "bidirectional"))
      (node (ref "U215") (pin "12") (pinfunction "12_COM1_12") (pintype "bidirectional"))
    )
    (net (code "38") (name "DIG2") (class "Default")
      (node (ref "P85") (pin "P$1") (pinfunction "P$1_P$1") (pintype "bidirectional"))
      (node (ref "U205") (pin "P$3") (pinfunction "P$3_P$3") (pintype "bidirectional"))
      (node (ref "U215") (pin "9") (pinfunction "9_COM2_9") (pintype "bidirectional"))
    )
    (net (code "39") (name "DIG3") (class "Default")
      (node (ref "P86") (pin "P$1") (pinfunction "P$1_P$1") (pintype "bidirectional"))
      (node (ref "U205") (pin "P$4") (pinfunction "P$4_P$4") (pintype "bidirectional"))
      (node (ref "U215") (pin "8") (pinfunction "8_COM3_8") (pintype "bidirectional"))
    )
    (net (code "40") (name "DIG4") (class "Default")
      (node (ref "P87") (pin "P$1") (pinfunction "P$1_P$1") (pintype "bidirectional"))
      (node (ref "U205") (pin "P$5") (pinfunction "P$5_P$5") (pintype "bidirectional"))
      (node (ref "U215") (pin "6") (pinfunction "6_COM4_6") (pintype "bidirectional"))
    )
    (net (code "41") (name "DP") (class "Default")
      (node (ref "P82") (pin "P$1") (pinfunction "P$1_P$1") (pintype "bidirectional"))
      (node (ref "U205") (pin "P$10") (pinfunction "P$10_P$10") (pintype "bidirectional"))
      (node (ref "U215") (pin "3") (pinfunction "3_DP_3") (pintype "bidirectional"))
    )
    (net (code "42") (name "DVI") (class "Default")
      (node (ref "C209") (pin "2") (pinfunction "2_2") (pintype "passive"))
      (node (ref "P51") (pin "P$1") (pinfunction "P$1_P$1") (pintype "bidirectional"))
      (node (ref "R271") (pin "2") (pinfunction "2_2") (pintype "passive"))
      (node (ref "U1") (pin "5") (pinfunction "DVI_5") (pintype "bidirectional"))
    )
    (net (code "43") (name "E") (class "Default")
      (node (ref "P79") (pin "P$1") (pinfunction "P$1_P$1") (pintype "bidirectional"))
      (node (ref "U205") (pin "P$13") (pinfunction "P$13_P$13") (pintype "bidirectional"))
      (node (ref "U215") (pin "1") (pinfunction "1_E_1") (pintype "bidirectional"))
    )
    (net (code "44") (name "E_LCD") (class "Default")
      (node (ref "P60") (pin "P$1") (pinfunction "P$1_P$1") (pintype "bidirectional"))
      (node (ref "U2") (pin "P$6") (pinfunction "P2_P$6") (pintype "bidirectional"))
      (node (ref "U8") (pin "P$6") (pinfunction "6_E_P$6") (pintype "bidirectional"))
    )
    (net (code "45") (name "F") (class "Default")
      (node (ref "P80") (pin "P$1") (pinfunction "P$1_P$1") (pintype "bidirectional"))
      (node (ref "U205") (pin "P$12") (pinfunction "P$12_P$12") (pintype "bidirectional"))
      (node (ref "U215") (pin "10") (pinfunction "10_F_10") (pintype "bidirectional"))
    )
    (net (code "46") (name "FB") (class "Default")
      (node (ref "C47") (pin "2") (pinfunction "2_2") (pintype "passive"))
      (node (ref "P4") (pin "P$1") (pinfunction "P$1_P$1") (pintype "bidirectional"))
      (node (ref "R75") (pin "1") (pinfunction "1_1") (pintype "passive"))
      (node (ref "R76") (pin "2") (pinfunction "2_2") (pintype "passive"))
      (node (ref "U10") (pin "3") (pinfunction "FB_3") (pintype "bidirectional"))
    )
    (net (code "47") (name "G") (class "Default")
      (node (ref "P81") (pin "P$1") (pinfunction "P$1_P$1") (pintype "bidirectional"))
      (node (ref "U205") (pin "P$11") (pinfunction "P$11_P$11") (pintype "bidirectional"))
      (node (ref "U215") (pin "5") (pinfunction "5_G_5") (pintype "bidirectional"))
    )
    (net (code "48") (name "GND") (class "Default")
      (node (ref "BT1") (pin "N") (pinfunction "-_N") (pintype "passive"))
      (node (ref "C1") (pin "2") (pinfunction "2_2") (pintype "passive"))
      (node (ref "C101") (pin "1") (pinfunction "1_1") (pintype "passive"))
      (node (ref "C102") (pin "1") (pinfunction "1_1") (pintype "passive"))
      (node (ref "C107") (pin "2") (pinfunction "2_2") (pintype "passive"))
      (node (ref "C108") (pin "2") (pinfunction "2_2") (pintype "passive"))
      (node (ref "C14") (pin "1") (pinfunction "1_1") (pintype "passive"))
      (node (ref "C16") (pin "1") (pinfunction "1_1") (pintype "passive"))
      (node (ref "C2") (pin "1") (pinfunction "1_1") (pintype "passive"))
      (node (ref "C20") (pin "2") (pinfunction "2_2") (pintype "passive"))
      (node (ref "C209") (pin "1") (pinfunction "1_1") (pintype "passive"))
      (node (ref "C21") (pin "2") (pinfunction "2_2") (pintype "passive"))
      (node (ref "C214") (pin "1") (pinfunction "1_1") (pintype "passive"))
      (node (ref "C22") (pin "2") (pinfunction "2_2") (pintype "passive"))
      (node (ref "C225") (pin "1") (pinfunction "1_1") (pintype "passive"))
      (node (ref "C25") (pin "1") (pinfunction "1_1") (pintype "passive"))
      (node (ref "C3") (pin "2") (pinfunction "2_2") (pintype "passive"))
      (node (ref "C30") (pin "1") (pinfunction "1_1") (pintype "passive"))
      (node (ref "C33") (pin "2") (pinfunction "2_2") (pintype "passive"))
      (node (ref "C34") (pin "2") (pinfunction "2_2") (pintype "passive"))
      (node (ref "C37") (pin "1") (pinfunction "1_1") (pintype "passive"))
      (node (ref "C4") (pin "1") (pinfunction "1_1") (pintype "passive"))
      (node (ref "C48") (pin "1") (pinfunction "1_1") (pintype "passive"))
      (node (ref "C5") (pin "1") (pinfunction "1_1") (pintype "passive"))
      (node (ref "C51") (pin "1") (pinfunction "1_1") (pintype "passive"))
      (node (ref "C53") (pin "1") (pinfunction "1_1") (pintype "passive"))
      (node (ref "C6") (pin "1") (pinfunction "1_1") (pintype "passive"))
      (node (ref "C7") (pin "1") (pinfunction "1_1") (pintype "passive"))
      (node (ref "C8") (pin "1") (pinfunction "1_1") (pintype "passive"))
      (node (ref "J10") (pin "1") (pinfunction "1_1") (pintype "bidirectional"))
      (node (ref "J101") (pin "3") (pinfunction "G_3") (pintype "bidirectional"))
      (node (ref "J14") (pin "P$1") (pinfunction "1_GND_P$1") (pintype "bidirectional"))
      (node (ref "J15") (pin "1") (pinfunction "1_1") (pintype "bidirectional"))
      (node (ref "J19") (pin "A1") (pinfunction "A1_A1") (pintype "bidirectional"))
      (node (ref "J19") (pin "A2") (pinfunction "A2_A2") (pintype "bidirectional"))
      (node (ref "J19") (pin "A3") (pinfunction "A3_A3") (pintype "bidirectional"))
      (node (ref "J19") (pin "A4") (pinfunction "A4_A4") (pintype "bidirectional"))
      (node (ref "J19") (pin "A5") (pinfunction "A5_A5") (pintype "bidirectional"))
      (node (ref "J19") (pin "A6") (pinfunction "A6_A6") (pintype "bidirectional"))
      (node (ref "J3") (pin "4") (pinfunction "4_4") (pintype "bidirectional"))
      (node (ref "J3") (pin "SS1") (pinfunction "SS1_SS1") (pintype "bidirectional"))
      (node (ref "J3") (pin "SS2") (pinfunction "SS2_SS2") (pintype "bidirectional"))
      (node (ref "J7") (pin "1") (pinfunction "1_1") (pintype "bidirectional"))
      (node (ref "J8") (pin "4") (pinfunction "4_4") (pintype "bidirectional"))
      (node (ref "J8") (pin "5") (pinfunction "SS1_5") (pintype "bidirectional"))
      (node (ref "J8") (pin "6") (pinfunction "SS2_6") (pintype "bidirectional"))
      (node (ref "P1") (pin "1") (pinfunction "1_1") (pintype "passive"))
      (node (ref "P29") (pin "P$1") (pinfunction "P$1_P$1") (pintype "bidirectional"))
      (node (ref "P39") (pin "P$1") (pinfunction "P$1_P$1") (pintype "bidirectional"))
      (node (ref "P43") (pin "P$1") (pinfunction "P$1_P$1") (pintype "bidirectional"))
      (node (ref "P45") (pin "P$1") (pinfunction "P$1_P$1") (pintype "bidirectional"))
      (node (ref "P50") (pin "P$1") (pinfunction "P$1_P$1") (pintype "bidirectional"))
      (node (ref "P52") (pin "P$1") (pinfunction "P$1_P$1") (pintype "bidirectional"))
      (node (ref "P56") (pin "P$1") (pinfunction "P$1_P$1") (pintype "bidirectional"))
      (node (ref "P57") (pin "P$1") (pinfunction "P$1_P$1") (pintype "bidirectional"))
      (node (ref "P67") (pin "P$1") (pinfunction "P$1_P$1") (pintype "bidirectional"))
      (node (ref "P71") (pin "P$1") (pinfunction "P$1_P$1") (pintype "bidirectional"))
      (node (ref "P74") (pin "P$1") (pinfunction "P$1_P$1") (pintype "bidirectional"))
      (node (ref "P88") (pin "P$1") (pinfunction "P$1_P$1") (pintype "bidirectional"))
      (node (ref "P91") (pin "P$1") (pinfunction "P$1_P$1") (pintype "bidirectional"))
      (node (ref "P94") (pin "P$1") (pinfunction "P$1_P$1") (pintype "bidirectional"))
      (node (ref "Q1") (pin "2") (pinfunction "E_2") (pintype "passive"))
      (node (ref "Q104") (pin "2") (pinfunction "E_2") (pintype "passive"))
      (node (ref "Q108") (pin "2") (pinfunction "E_2") (pintype "passive"))
      (node (ref "Q115") (pin "2") (pinfunction "E_2") (pintype "passive"))
      (node (ref "R101") (pin "1") (pinfunction "1_1") (pintype "passive"))
      (node (ref "R108") (pin "1") (pinfunction "1_1") (pintype "passive"))
      (node (ref "R238") (pin "1") (pinfunction "1_1") (pintype "passive"))
      (node (ref "R268") (pin "1") (pinfunction "1_1") (pintype "passive"))
      (node (ref "R273") (pin "1") (pinfunction "1_1") (pintype "passive"))
      (node (ref "R280") (pin "1") (pinfunction "1_1") (pintype "passive"))
      (node (ref "R307") (pin "2") (pinfunction "2_2") (pintype "passive"))
      (node (ref "R324") (pin "2") (pinfunction "2_2") (pintype "passive"))
      (node (ref "R4") (pin "1") (pinfunction "1_1") (pintype "passive"))
      (node (ref "R76") (pin "1") (pinfunction "1_1") (pintype "passive"))
      (node (ref "U1") (pin "3") (pinfunction "GND\\_3") (pintype "bidirectional"))
      (node (ref "U10") (pin "2") (pinfunction "GND_2") (pintype "bidirectional"))
      (node (ref "U101") (pin "7") (pinfunction "VSS_7") (pintype "power_in"))
      (node (ref "U2") (pin "P$8") (pinfunction "VSS_P$8") (pintype "bidirectional"))
      (node (ref "U205") (pin "P$1") (pinfunction "P$1_P$1") (pintype "bidirectional"))
      (node (ref "U3") (pin "3") (pinfunction "GND_3") (pintype "power_in"))
      (node (ref "U309") (pin "2") (pinfunction "P$2_2") (pintype "bidirectional"))
      (node (ref "U5") (pin "3") (pinfunction "GND_3") (pintype "bidirectional"))
      (node (ref "U7") (pin "1") (pinfunction "GND_1") (pintype "bidirectional"))
      (node (ref "U8") (pin "P$1") (pinfunction "1_VSS_P$1") (pintype "bidirectional"))
      (node (ref "U9") (pin "4") (pinfunction "GND_4") (pintype "bidirectional"))
    )
    (net (code "49") (name "IB") (class "Default")
      (node (ref "P98") (pin "P$1") (pinfunction "P$1_P$1") (pintype "bidirectional"))
      (node (ref "R108") (pin "2") (pinfunction "2_2") (pintype "passive"))
      (node (ref "U101") (pin "10") (pinfunction "IB_10") (pintype "bidirectional"))
    )
    (net (code "50") (name "LED") (class "Default")
      (node (ref "P42") (pin "P$1") (pinfunction "P$1_P$1") (pintype "bidirectional"))
      (node (ref "Q1") (pin "1") (pinfunction "B_1") (pintype "passive"))
      (node (ref "R4") (pin "2") (pinfunction "2_2") (pintype "passive"))
      (node (ref "R5") (pin "1") (pinfunction "1_1") (pintype "passive"))
    )
    (net (code "51") (name "LIGHT") (class "Default")
      (node (ref "P61") (pin "P$1") (pinfunction "P$1_P$1") (pintype "bidirectional"))
      (node (ref "R321") (pin "2") (pinfunction "2_2") (pintype "passive"))
      (node (ref "U2") (pin "P$7") (pinfunction "P3_P$7") (pintype "bidirectional"))
    )
    (net (code "52") (name "Net-(BT1-+)") (class "Default")
      (node (ref "BT1") (pin "P") (pinfunction "+_P") (pintype "passive"))
      (node (ref "U9") (pin "8") (pinfunction "VCC1_8") (pintype "bidirectional"))
    )
    (net (code "53") (name "Net-(C103-Pad1)") (class "Default")
      (node (ref "C103") (pin "1") (pinfunction "1_1") (pintype "passive"))
      (node (ref "R103") (pin "1") (pinfunction "1_1") (pintype "passive"))
    )
    (net (code "54") (name "Net-(C225-Pad2)") (class "Default")
      (node (ref "C225") (pin "2") (pinfunction "2_2") (pintype "passive"))
      (node (ref "R106") (pin "1") (pinfunction "1_1") (pintype "passive"))
    )
    (net (code "55") (name "Net-(D11-A)") (class "Default")
      (node (ref "D11") (pin "1") (pinfunction "A_1") (pintype "passive"))
      (node (ref "R7") (pin "2") (pinfunction "2_2") (pintype "passive"))
    )
    (net (code "56") (name "Net-(D11-C)") (class "Default")
      (node (ref "D11") (pin "2") (pinfunction "C_2") (pintype "passive"))
      (node (ref "Q1") (pin "3") (pinfunction "C_3") (pintype "passive"))
    )
    (net (code "57") (name "Net-(J14-2_ECHO)") (class "Default")
      (node (ref "J14") (pin "P$2") (pinfunction "2_ECHO_P$2") (pintype "bidirectional"))
      (node (ref "R299") (pin "1") (pinfunction "1_1") (pintype "passive"))
    )
    (net (code "58") (name "Net-(K2-Pad4)") (class "Default")
      (node (ref "K2") (pin "4") (pinfunction "4_4") (pintype "bidirectional"))
      (node (ref "R274") (pin "2") (pinfunction "2_2") (pintype "passive"))
    )
    (net (code "59") (name "Net-(Q104-C)") (class "Default")
      (node (ref "J313") (pin "P$2") (pinfunction "P$2_P$2") (pintype "bidirectional"))
      (node (ref "Q104") (pin "3") (pinfunction "C_3") (pintype "passive"))
    )
    (net (code "60") (name "Net-(Q108-B)") (class "Default")
      (node (ref "Q108") (pin "1") (pinfunction "B_1") (pintype "passive"))
      (node (ref "R321") (pin "1") (pinfunction "1_1") (pintype "passive"))
      (node (ref "R324") (pin "1") (pinfunction "1_1") (pintype "passive"))
    )
    (net (code "61") (name "Net-(Q108-C)") (class "Default")
      (node (ref "Q108") (pin "3") (pinfunction "C_3") (pintype "passive"))
      (node (ref "U8") (pin "P$16") (pinfunction "16_LED_K_P$16") (pintype "bidirectional"))
    )
    (net (code "62") (name "Net-(Q115-C)") (class "Default")
      (node (ref "Q115") (pin "3") (pinfunction "C_3") (pintype "passive"))
      (node (ref "Q3") (pin "1") (pinfunction "G_1") (pintype "bidirectional"))
      (node (ref "R81") (pin "1") (pinfunction "1_1") (pintype "passive"))
    )
    (net (code "63") (name "Net-(R104-Pad1)") (class "Default")
      (node (ref "R104") (pin "1") (pinfunction "1_1") (pintype "passive"))
      (node (ref "R15") (pin "1") (pinfunction "1_1") (pintype "passive"))
    )
    (net (code "64") (name "Net-(R268-3)") (class "Default")
      (node (ref "R268") (pin "2") (pinfunction "3_2") (pintype "passive"))
      (node (ref "U8") (pin "P$3") (pinfunction "3_V0_P$3") (pintype "bidirectional"))
    )
    (net (code "65") (name "Net-(U1-ADDR)") (class "Default")
      (node (ref "R237") (pin "1") (pinfunction "1_1") (pintype "passive"))
      (node (ref "R238") (pin "2") (pinfunction "2_2") (pintype "passive"))
      (node (ref "U1") (pin "2") (pinfunction "ADDR_2") (pintype "bidirectional"))
    )
    (net (code "66") (name "Net-(U2-A0)") (class "Default")
      (node (ref "R17") (pin "2") (pinfunction "2_2") (pintype "passive"))
      (node (ref "U2") (pin "P$1") (pinfunction "A0_P$1") (pintype "bidirectional"))
    )
    (net (code "67") (name "Net-(U2-A1)") (class "Default")
      (node (ref "R87") (pin "2") (pinfunction "2_2") (pintype "passive"))
      (node (ref "U2") (pin "P$2") (pinfunction "A1_P$2") (pintype "bidirectional"))
    )
    (net (code "68") (name "Net-(U2-A2)") (class "Default")
      (node (ref "R89") (pin "2") (pinfunction "2_2") (pintype "passive"))
      (node (ref "U2") (pin "P$3") (pinfunction "A2_P$3") (pintype "bidirectional"))
    )
    (net (code "69") (name "Net-(U10-EN)") (class "Default")
      (node (ref "R28") (pin "2") (pinfunction "2_2") (pintype "passive"))
      (node (ref "U10") (pin "4") (pinfunction "EN_4") (pintype "bidirectional"))
    )
    (net (code "70") (name "Net-(U10-LX)") (class "Default")
      (node (ref "D10") (pin "+") (pinfunction "+_+") (pintype "passive"))
      (node (ref "L8") (pin "2") (pinfunction "2_2") (pintype "bidirectional"))
      (node (ref "U10") (pin "1") (pinfunction "LX_1") (pintype "bidirectional"))
    )
    (net (code "71") (name "Net-(U101-A)") (class "Default")
      (node (ref "R113") (pin "2") (pinfunction "2_2") (pintype "passive"))
      (node (ref "U101") (pin "1") (pinfunction "A_1") (pintype "bidirectional"))
    )
    (net (code "72") (name "Net-(U101-RR1)") (class "Default")
      (node (ref "R111") (pin "1") (pinfunction "1_1") (pintype "passive"))
      (node (ref "U101") (pin "3") (pinfunction "RR1_3") (pintype "bidirectional"))
    )
    (net (code "73") (name "Net-(U101-RR2)") (class "Default")
      (node (ref "R110") (pin "2") (pinfunction "2_2") (pintype "passive"))
      (node (ref "U101") (pin "6") (pinfunction "RR2_6") (pintype "bidirectional"))
    )
    (net (code "74") (name "Net-(U101-VC)") (class "Default")
      (node (ref "R109") (pin "2") (pinfunction "2_2") (pintype "passive"))
      (node (ref "U101") (pin "9") (pinfunction "VC_9") (pintype "bidirectional"))
    )
    (net (code "75") (name "OSC0") (class "Default")
      (node (ref "C5") (pin "2") (pinfunction "2_2") (pintype "passive"))
      (node (ref "P47") (pin "P$1") (pinfunction "P$1_P$1") (pintype "bidirectional"))
      (node (ref "U9") (pin "3") (pinfunction "X2_3") (pintype "bidirectional"))
      (node (ref "Y1") (pin "4") (pinfunction "4_4") (pintype "bidirectional"))
    )
    (net (code "76") (name "OSC1") (class "Default")
      (node (ref "C1") (pin "1") (pinfunction "1_1") (pintype "passive"))
      (node (ref "P46") (pin "P$1") (pinfunction "P$1_P$1") (pintype "bidirectional"))
      (node (ref "U9") (pin "2") (pinfunction "X1_2") (pintype "bidirectional"))
      (node (ref "Y1") (pin "1") (pinfunction "1_1") (pintype "bidirectional"))
    )
    (net (code "77") (name "PIR") (class "Default")
      (node (ref "P96") (pin "P$1") (pinfunction "P$1_P$1") (pintype "bidirectional"))
      (node (ref "R112") (pin "2") (pinfunction "2_2") (pintype "passive"))
      (node (ref "U101") (pin "2") (pinfunction "VO_2") (pintype "bidirectional"))
    )
    (net (code "78") (name "RC1") (class "Default")
      (node (ref "C108") (pin "1") (pinfunction "1_1") (pintype "passive"))
      (node (ref "P104") (pin "P$1") (pinfunction "P$1_P$1") (pintype "bidirectional"))
      (node (ref "R111") (pin "2") (pinfunction "2_2") (pintype "passive"))
      (node (ref "U101") (pin "4") (pinfunction "RC1_4") (pintype "bidirectional"))
    )
    (net (code "79") (name "RC2") (class "Default")
      (node (ref "C107") (pin "1") (pinfunction "1_1") (pintype "passive"))
      (node (ref "P105") (pin "P$1") (pinfunction "P$1_P$1") (pintype "bidirectional"))
      (node (ref "R110") (pin "1") (pinfunction "1_1") (pintype "passive"))
      (node (ref "U101") (pin "5") (pinfunction "RC2_5") (pintype "bidirectional"))
    )
    (net (code "80") (name "RED") (class "Default")
      (node (ref "D130") (pin "2") (pinfunction "2_K_2") (pintype "passive"))
      (node (ref "P5") (pin "P$1") (pinfunction "P$1_P$1") (pintype "bidirectional"))
      (node (ref "R307") (pin "1") (pinfunction "1_1") (pintype "passive"))
    )
    (net (code "81") (name "RS") (class "Default")
      (node (ref "P58") (pin "P$1") (pinfunction "P$1_P$1") (pintype "bidirectional"))
      (node (ref "U2") (pin "P$4") (pinfunction "P0_P$4") (pintype "bidirectional"))
      (node (ref "U8") (pin "P$4") (pinfunction "4_RS_P$4") (pintype "bidirectional"))
    )
    (net (code "82") (name "RW") (class "Default")
      (node (ref "P59") (pin "P$1") (pinfunction "P$1_P$1") (pintype "bidirectional"))
      (node (ref "U2") (pin "P$5") (pinfunction "P1_P$5") (pintype "bidirectional"))
      (node (ref "U8") (pin "P$5") (pinfunction "5_RW_P$5") (pintype "bidirectional"))
    )
    (net (code "83") (name "S") (class "Default")
      (node (ref "C101") (pin "2") (pinfunction "2_2") (pintype "passive"))
      (node (ref "J101") (pin "2") (pinfunction "S_2") (pintype "bidirectional"))
      (node (ref "P95") (pin "P$1") (pinfunction "P$1_P$1") (pintype "bidirectional"))
      (node (ref "R101") (pin "2") (pinfunction "2_2") (pintype "passive"))
      (node (ref "R102") (pin "2") (pinfunction "2_2") (pintype "passive"))
    )
    (net (code "84") (name "SEN_3V3") (class "Default")
      (node (ref "C102") (pin "2") (pinfunction "2_2") (pintype "passive"))
      (node (ref "C14") (pin "2") (pinfunction "2_2") (pintype "passive"))
      (node (ref "C20") (pin "1") (pinfunction "1_1") (pintype "passive"))
      (node (ref "C214") (pin "2") (pinfunction "2_2") (pintype "passive"))
      (node (ref "C22") (pin "1") (pinfunction "1_1") (pintype "passive"))
      (node (ref "C25") (pin "2") (pinfunction "2_2") (pintype "passive"))
      (node (ref "C34") (pin "1") (pinfunction "1_1") (pintype "passive"))
      (node (ref "C4") (pin "2") (pinfunction "2_2") (pintype "passive"))
      (node (ref "J101") (pin "1") (pinfunction "D_1") (pintype "bidirectional"))
      (node (ref "J14") (pin "P$4") (pinfunction "4VCC_P$4") (pintype "bidirectional"))
      (node (ref "J19") (pin "A10") (pinfunction "A10_A10") (pintype "bidirectional"))
      (node (ref "J19") (pin "A11") (pinfunction "A11_A11") (pintype "bidirectional"))
      (node (ref "J19") (pin "A12") (pinfunction "A12_A12") (pintype "bidirectional"))
      (node (ref "J19") (pin "A13") (pinfunction "A13_A13") (pintype "bidirectional"))
      (node (ref "J19") (pin "A14") (pinfunction "A14_A14") (pintype "bidirectional"))
      (node (ref "J19") (pin "A9") (pinfunction "A9_A9") (pintype "bidirectional"))
      (node (ref "P1") (pin "3") (pinfunction "2_3") (pintype "passive"))
      (node (ref "P26") (pin "P$1") (pinfunction "P$1_P$1") (pintype "bidirectional"))
      (node (ref "P36") (pin "P$1") (pinfunction "P$1_P$1") (pintype "bidirectional"))
      (node (ref "P41") (pin "P$1") (pinfunction "P$1_P$1") (pintype "bidirectional"))
      (node (ref "P48") (pin "P$1") (pinfunction "P$1_P$1") (pintype "bidirectional"))
      (node (ref "P49") (pin "P$1") (pinfunction "P$1_P$1") (pintype "bidirectional"))
      (node (ref "P7") (pin "P$1") (pinfunction "P$1_P$1") (pintype "bidirectional"))
      (node (ref "P70") (pin "P$1") (pinfunction "P$1_P$1") (pintype "bidirectional"))
      (node (ref "P89") (pin "P$1") (pinfunction "P$1_P$1") (pintype "bidirectional"))
      (node (ref "P97") (pin "P$1") (pinfunction "P$1_P$1") (pintype "bidirectional"))
      (node (ref "Q2") (pin "1") (pinfunction "G_1") (pintype "passive"))
      (node (ref "Q4") (pin "1") (pinfunction "G_1") (pintype "passive"))
      (node (ref "Q405") (pin "1") (pinfunction "G_1") (pintype "passive"))
      (node (ref "R1") (pin "1") (pinfunction "1_1") (pintype "passive"))
      (node (ref "R109") (pin "1") (pinfunction "1_1") (pintype "passive"))
      (node (ref "R113") (pin "1") (pinfunction "1_1") (pintype "passive"))
      (node (ref "R12") (pin "1") (pinfunction "1_1") (pintype "passive"))
      (node (ref "R13") (pin "1") (pinfunction "1_1") (pintype "passive"))
      (node (ref "R237") (pin "2") (pinfunction "2_2") (pintype "passive"))
      (node (ref "R271") (pin "1") (pinfunction "1_1") (pintype "passive"))
      (node (ref "R3") (pin "1") (pinfunction "1_1") (pintype "passive"))
      (node (ref "R301") (pin "1") (pinfunction "1_1") (pintype "passive"))
      (node (ref "R422") (pin "2") (pinfunction "2_2") (pintype "passive"))
      (node (ref "R6") (pin "1") (pinfunction "1_1") (pintype "passive"))
      (node (ref "R63") (pin "2") (pinfunction "2_2") (pintype "passive"))
      (node (ref "U1") (pin "1") (pinfunction "VCC_1") (pintype "bidirectional"))
      (node (ref "U101") (pin "11") (pinfunction "VDD_11") (pintype "power_in"))
      (node (ref "U101") (pin "8") (pinfunction "~{RESET}_8") (pintype "input"))
      (node (ref "U3") (pin "1") (pinfunction "VCC_1") (pintype "power_in"))
      (node (ref "U309") (pin "1") (pinfunction "P$1_1") (pintype "bidirectional"))
      (node (ref "U7") (pin "2") (pinfunction "VOUT_2") (pintype "bidirectional"))
      (node (ref "U7") (pin "4") (pinfunction "TAB_4") (pintype "bidirectional"))
      (node (ref "U9") (pin "1") (pinfunction "VCC2_1") (pintype "bidirectional"))
    )
    (net (code "85") (name "SERVO") (class "Default")
      (node (ref "J3") (pin "1") (pinfunction "1_1") (pintype "bidirectional"))
      (node (ref "P93") (pin "P$1") (pinfunction "P$1_P$1") (pintype "bidirectional"))
      (node (ref "Q405") (pin "3") (pinfunction "D_3") (pintype "passive"))
      (node (ref "R329") (pin "1") (pinfunction "1_1") (pintype "passive"))
      (node (ref "R423") (pin "2") (pinfunction "2_2") (pintype "passive"))
    )
    (net (code "86") (name "USB_D_N") (class "Default")
      (node (ref "J12") (pin "1") (pinfunction "1_1") (pintype "bidirectional"))
      (node (ref "J2") (pin "1") (pinfunction "1_1") (pintype "bidirectional"))
      (node (ref "J6") (pin "1") (pinfunction "1_1") (pintype "bidirectional"))
      (node (ref "J8") (pin "3") (pinfunction "3_3") (pintype "bidirectional"))
    )
    (net (code "87") (name "USB_D_P") (class "Default")
      (node (ref "J13") (pin "1") (pinfunction "1_1") (pintype "bidirectional"))
      (node (ref "J5") (pin "1") (pinfunction "1_1") (pintype "bidirectional"))
      (node (ref "J8") (pin "2") (pinfunction "2_2") (pintype "bidirectional"))
      (node (ref "J9") (pin "1") (pinfunction "1_1") (pintype "bidirectional"))
    )
    (net (code "88") (name "VBUS") (class "Default")
      (node (ref "J4") (pin "1") (pinfunction "1_1") (pintype "bidirectional"))
      (node (ref "J8") (pin "1") (pinfunction "1_1") (pintype "bidirectional"))
      (node (ref "K2") (pin "1") (pinfunction "1_1") (pintype "bidirectional"))
      (node (ref "P30") (pin "P$1") (pinfunction "P$1_P$1") (pintype "bidirectional"))
      (node (ref "Q3") (pin "2") (pinfunction "S_2") (pintype "bidirectional"))
      (node (ref "R81") (pin "2") (pinfunction "2_2") (pintype "passive"))
    )
    (net (code "89") (name "VCC_5V") (class "Default")
      (node (ref "C16") (pin "2") (pinfunction "2_2") (pintype "passive"))
      (node (ref "C21") (pin "1") (pinfunction "1_1") (pintype "passive"))
      (node (ref "C30") (pin "2") (pinfunction "2_2") (pintype "passive"))
      (node (ref "C33") (pin "1") (pinfunction "1_1") (pintype "passive"))
      (node (ref "C37") (pin "2") (pinfunction "2_2") (pintype "passive"))
      (node (ref "C47") (pin "1") (pinfunction "1_1") (pintype "passive"))
      (node (ref "C48") (pin "2") (pinfunction "2_2") (pintype "passive"))
      (node (ref "C6") (pin "2") (pinfunction "2_2") (pintype "passive"))
      (node (ref "C7") (pin "2") (pinfunction "2_2") (pintype "passive"))
      (node (ref "D10") (pin "-") (pinfunction "-_-") (pintype "passive"))
      (node (ref "D130") (pin "1") (pinfunction "1_A_1") (pintype "passive"))
      (node (ref "J3") (pin "3") (pinfunction "3_3") (pintype "bidirectional"))
      (node (ref "P3") (pin "P$1") (pinfunction "P$1_P$1") (pintype "bidirectional"))
      (node (ref "P40") (pin "P$1") (pinfunction "P$1_P$1") (pintype "bidirectional"))
      (node (ref "P54") (pin "P$1") (pinfunction "P$1_P$1") (pintype "bidirectional"))
      (node (ref "P55") (pin "P$1") (pinfunction "P$1_P$1") (pintype "bidirectional"))
      (node (ref "P6") (pin "P$1") (pinfunction "P$1_P$1") (pintype "bidirectional"))
      (node (ref "P66") (pin "P$1") (pinfunction "P$1_P$1") (pintype "bidirectional"))
      (node (ref "P73") (pin "P$1") (pinfunction "P$1_P$1") (pintype "bidirectional"))
      (node (ref "P83") (pin "P$1") (pinfunction "P$1_P$1") (pintype "bidirectional"))
      (node (ref "P92") (pin "P$1") (pinfunction "P$1_P$1") (pintype "bidirectional"))
      (node (ref "R17") (pin "1") (pinfunction "1_1") (pintype "passive"))
      (node (ref "R18") (pin "1") (pinfunction "1_1") (pintype "passive"))
      (node (ref "R19") (pin "1") (pinfunction "1_1") (pintype "passive"))
      (node (ref "R2") (pin "1") (pinfunction "1_1") (pintype "passive"))
      (node (ref "R268") (pin "3") (pinfunction "2_3") (pintype "passive"))
      (node (ref "R283") (pin "1") (pinfunction "1_1") (pintype "passive"))
      (node (ref "R423") (pin "1") (pinfunction "1_1") (pintype "passive"))
      (node (ref "R7") (pin "1") (pinfunction "1_1") (pintype "passive"))
      (node (ref "R75") (pin "2") (pinfunction "2_2") (pintype "passive"))
      (node (ref "R87") (pin "1") (pinfunction "1_1") (pintype "passive"))
      (node (ref "R89") (pin "1") (pinfunction "1_1") (pintype "passive"))
      (node (ref "R9") (pin "1") (pinfunction "1_1") (pintype "passive"))
      (node (ref "U2") (pin "P$16") (pinfunction "VDD_P$16") (pintype "bidirectional"))
      (node (ref "U205") (pin "P$20") (pinfunction "P$20_P$20") (pintype "bidirectional"))
      (node (ref "U5") (pin "1") (pinfunction "VCC_1") (pintype "bidirectional"))
      (node (ref "U7") (pin "3") (pinfunction "VIN_3") (pintype "bidirectional"))
      (node (ref "U8") (pin "P$15") (pinfunction "15_LEDA_P$15") (pintype "bidirectional"))
      (node (ref "U8") (pin "P$2") (pinfunction "2_VDD_P$2") (pintype "bidirectional"))
    )
    (net (code "90") (name "VIB") (class "Default")
      (node (ref "P68") (pin "P$1") (pinfunction "P$1_P$1") (pintype "bidirectional"))
      (node (ref "Q104") (pin "1") (pinfunction "B_1") (pintype "passive"))
      (node (ref "R280") (pin "2") (pinfunction "2_2") (pintype "passive"))
      (node (ref "R282") (pin "2") (pinfunction "2_2") (pintype "passive"))
    )
    (net (code "91") (name "VIN") (class "Default")
      (node (ref "C51") (pin "2") (pinfunction "2_2") (pintype "passive"))
      (node (ref "C53") (pin "2") (pinfunction "2_2") (pintype "passive"))
      (node (ref "J1") (pin "1") (pinfunction "1_1") (pintype "bidirectional"))
      (node (ref "J11") (pin "1") (pinfunction "1_1") (pintype "bidirectional"))
      (node (ref "L8") (pin "1") (pinfunction "1_1") (pintype "bidirectional"))
      (node (ref "P2") (pin "P$1") (pinfunction "P$1_P$1") (pintype "bidirectional"))
      (node (ref "P31") (pin "P$1") (pinfunction "P$1_P$1") (pintype "bidirectional"))
      (node (ref "Q3") (pin "3") (pinfunction "D_3") (pintype "bidirectional"))
      (node (ref "R28") (pin "1") (pinfunction "1_1") (pintype "passive"))
      (node (ref "U10") (pin "5") (pinfunction "VCC_5") (pintype "bidirectional"))
    )
    (net (code "92") (name "unconnected-(J3-Pad2)") (class "Default")
      (node (ref "J3") (pin "2") (pinfunction "2_2") (pintype "bidirectional"))
    )
    (net (code "93") (name "unconnected-(K2-Pad2)") (class "Default")
      (node (ref "K2") (pin "2") (pinfunction "2_2") (pintype "bidirectional"))
    )
    (net (code "94") (name "unconnected-(K2-Pad3)") (class "Default")
      (node (ref "K2") (pin "3") (pinfunction "3_3") (pintype "bidirectional"))
    )
    (net (code "95") (name "unconnected-(U2-INT#-PadP$13)") (class "Default")
      (node (ref "U2") (pin "P$13") (pinfunction "INT#_P$13") (pintype "bidirectional"))
    )
    (net (code "96") (name "unconnected-(U8-7_D0-PadP$7)") (class "Default")
      (node (ref "U8") (pin "P$7") (pinfunction "7_D0_P$7") (pintype "bidirectional"))
    )
    (net (code "97") (name "unconnected-(U8-8_D1-PadP$8)") (class "Default")
      (node (ref "U8") (pin "P$8") (pinfunction "8_D1_P$8") (pintype "bidirectional"))
    )
    (net (code "98") (name "unconnected-(U8-9_D2-PadP$9)") (class "Default")
      (node (ref "U8") (pin "P$9") (pinfunction "9_D2_P$9") (pintype "bidirectional"))
    )
    (net (code "99") (name "unconnected-(U8-10_D3-PadP$10)") (class "Default")
      (node (ref "U8") (pin "P$10") (pinfunction "10_D3_P$10") (pintype "bidirectional"))
    )
    (net (code "100") (name "unconnected-(U10-OC-Pad6)") (class "Default")
      (node (ref "U10") (pin "6") (pinfunction "OC_6") (pintype "bidirectional"))
    )
    (net (code "101") (name "unconnected-(U205-PadP$6)") (class "Default")
      (node (ref "U205") (pin "P$6") (pinfunction "P$6_P$6") (pintype "bidirectional"))
    )
    (net (code "102") (name "unconnected-(U205-PadP$7)") (class "Default")
      (node (ref "U205") (pin "P$7") (pinfunction "P$7_P$7") (pintype "bidirectional"))
    )
    (net (code "103") (name "unconnected-(U205-PadP$8)") (class "Default")
      (node (ref "U205") (pin "P$8") (pinfunction "P$8_P$8") (pintype "bidirectional"))
    )
    (net (code "104") (name "unconnected-(U205-PadP$9)") (class "Default")
      (node (ref "U205") (pin "P$9") (pinfunction "P$9_P$9") (pintype "bidirectional"))
    )
    (net (code "105") (name "unconnected-(Y1-Pad2)") (class "Default")
      (node (ref "Y1") (pin "2") (pinfunction "2_2") (pintype "bidirectional"))
    )
    (net (code "106") (name "unconnected-(Y1-Pad3)") (class "Default")
      (node (ref "Y1") (pin "3") (pinfunction "3_3") (pintype "bidirectional"))
    )
  )
)
